# SCH_ESP32_Controller_PoE_2022-09-25.net
KiCad netlist of a schematic drawn in EasyEDA
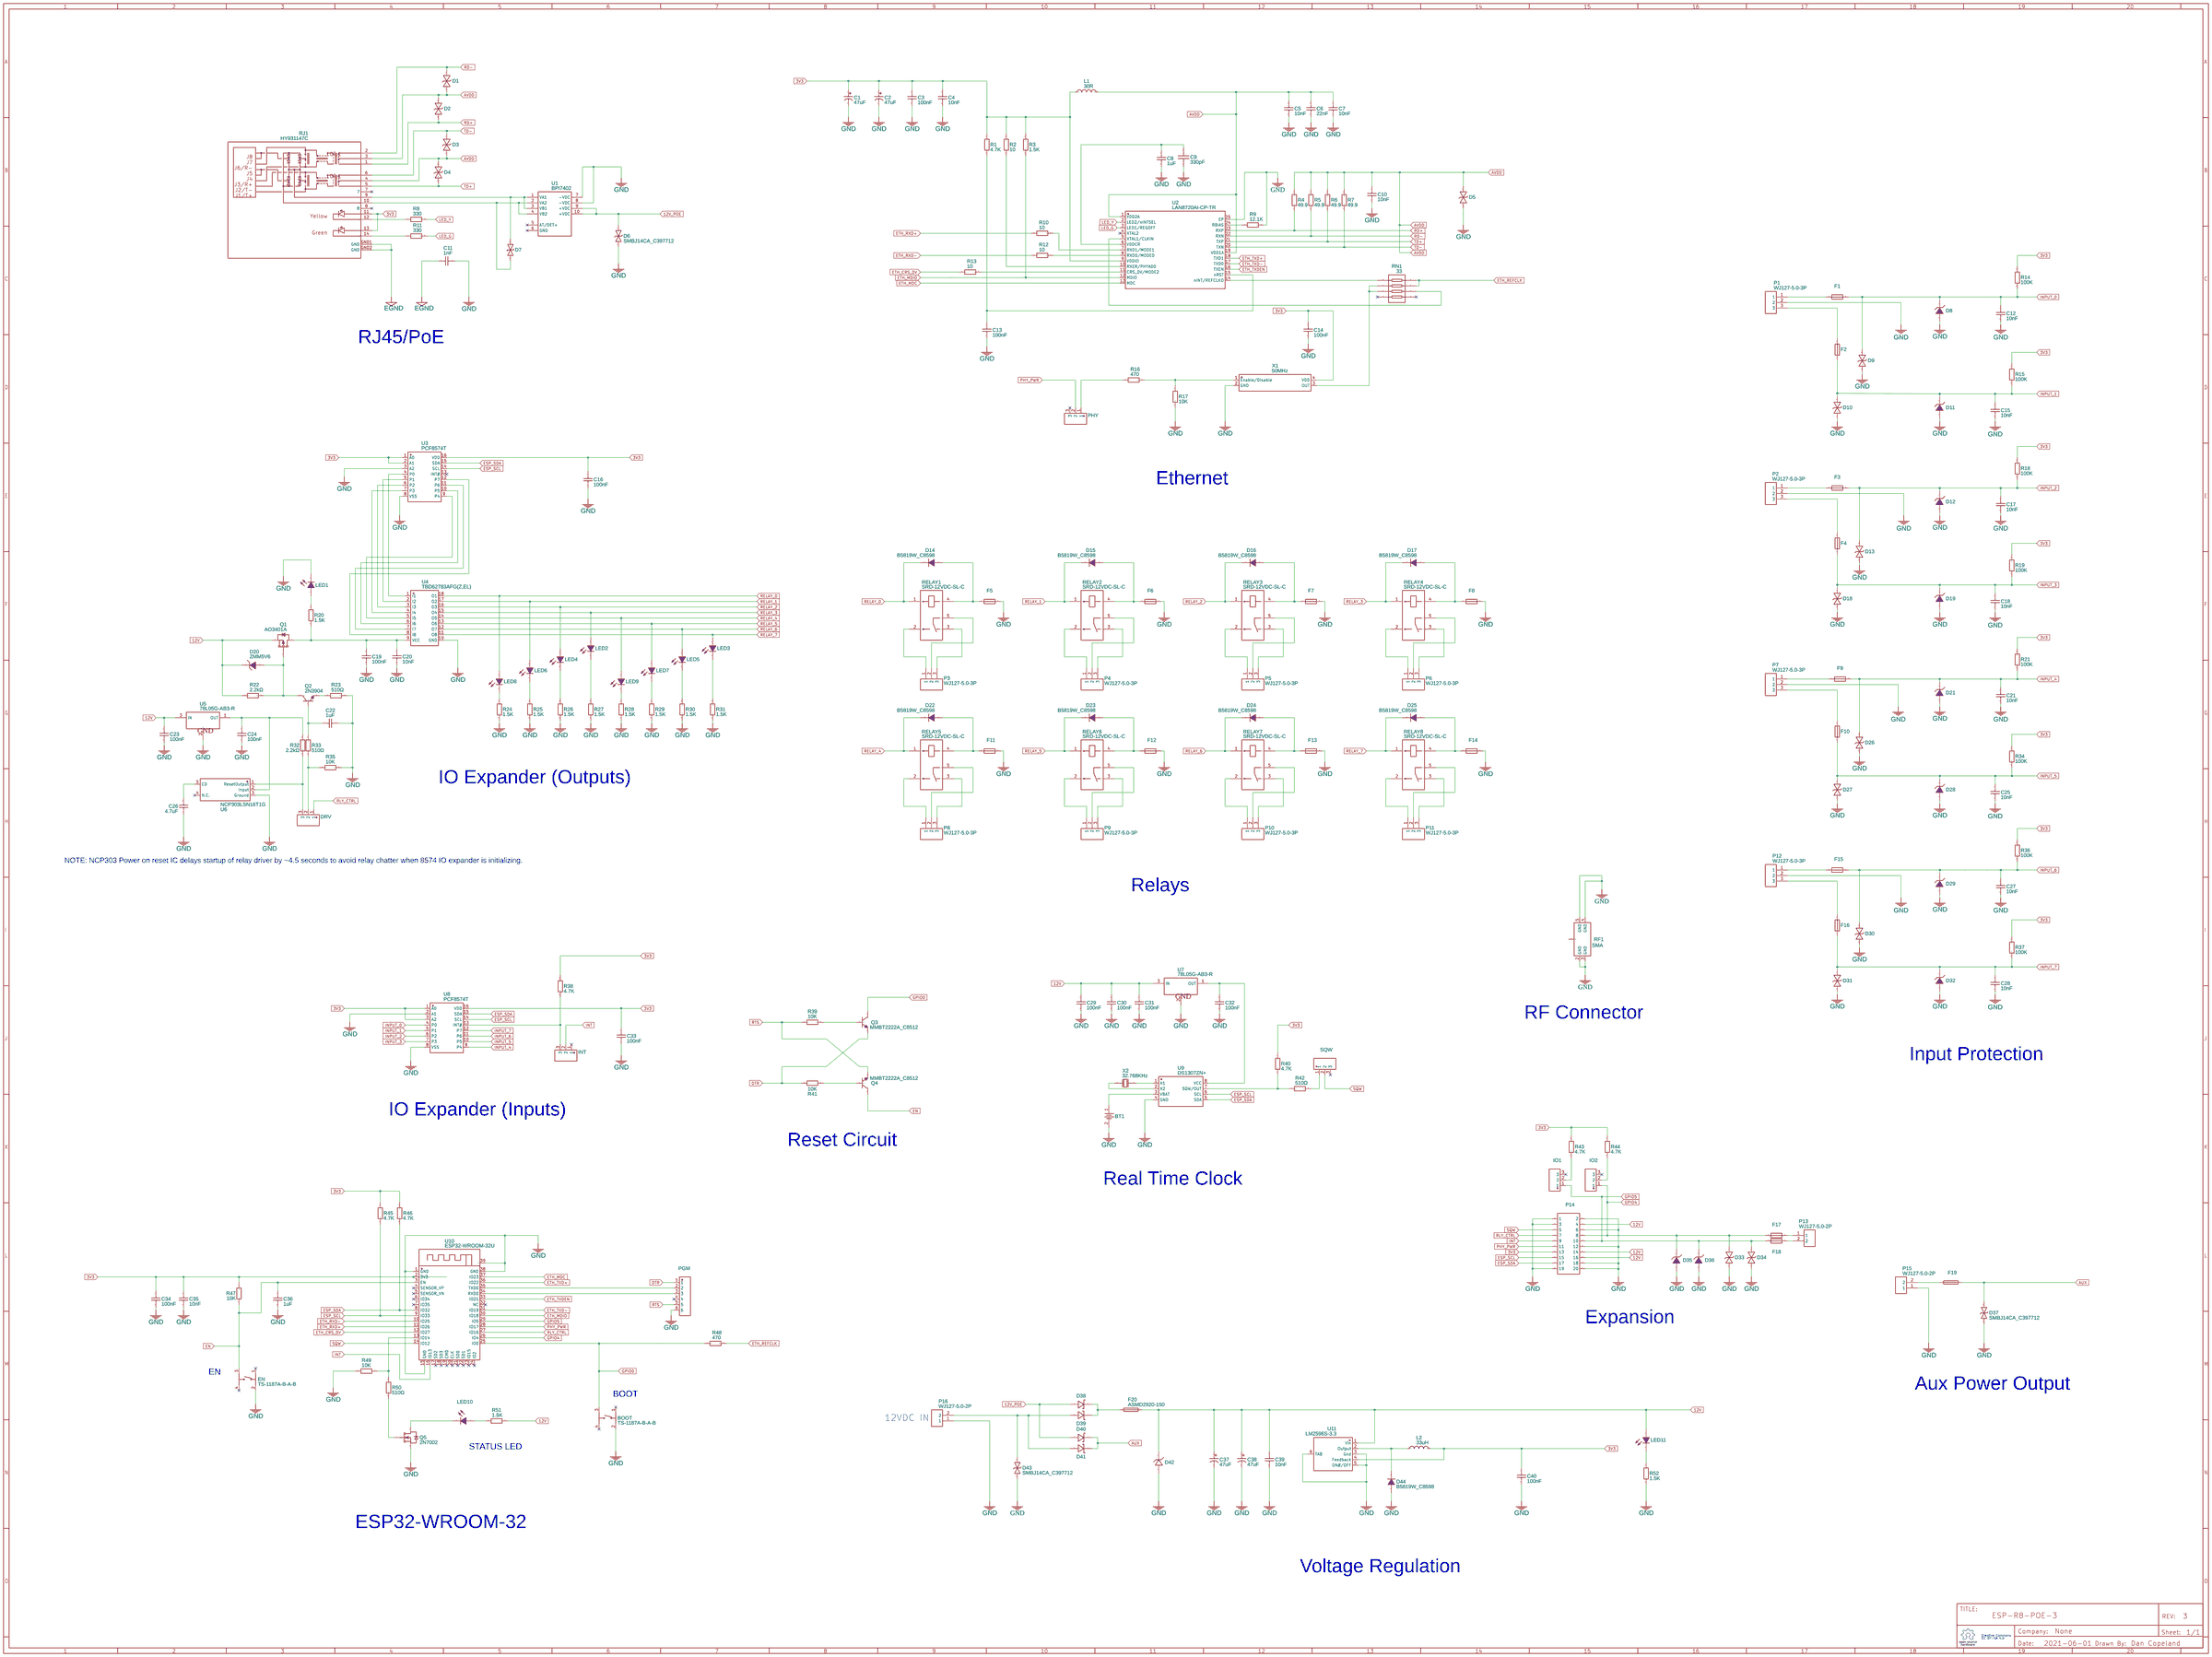
[diagram p0: schematic sheet]

(export (version "E")
  (design (tool "Eeschema 10.0.6"))
  (components
    (comp (ref "BOOT")
      (value "TS-1187A-B-A-B")
      (fields (field (name "BOM_Supplier Part") "C318884"))
      (libsource (lib "") (part "TS-1187A-B-A-B_1"))
    )
    (comp (ref "BT1")
      (value "BS-12-A1AJ002-F")
      (fields (field (name "BOM_Supplier Part") "C964720"))
      (libsource (lib "") (part "BS-12-A1AJ002-F"))
    )
    (comp (ref "C1")
      (value "47uF")
      (fields
        (field (name "BOM_Manufacturer Part") "16MS747MEFC5X7")
        (field (name "BOM_Supplier Part") "C108854")
      )
      (libsource (lib "") (part "16MS747MEFC5X7"))
    )
    (comp (ref "C2")
      (value "47uF")
      (fields
        (field (name "BOM_Manufacturer Part") "16MS747MEFC5X7")
        (field (name "BOM_Supplier Part") "C108854")
      )
      (libsource (lib "") (part "16MS747MEFC5X7"))
    )
    (comp (ref "C3")
      (value "100nF")
      (fields
        (field (name "BOM_Manufacturer Part") "CL05B104KO5NNNC")
        (field (name "BOM_Supplier Part") "C1525")
      )
      (libsource (lib "") (part "CL05B104KO5NNNC"))
    )
    (comp (ref "C4")
      (value "10nF")
      (fields
        (field (name "BOM_Manufacturer Part") "CL05B103KB5NNNC")
        (field (name "BOM_Supplier Part") "C15195")
      )
      (libsource (lib "") (part "CL05B103KB5NNNC"))
    )
    (comp (ref "C5")
      (value "10nF")
      (fields
        (field (name "BOM_Manufacturer Part") "CL05B103KB5NNNC")
        (field (name "BOM_Supplier Part") "C15195")
      )
      (libsource (lib "") (part "CL05B103KB5NNNC"))
    )
    (comp (ref "C6")
      (value "22nF")
      (fields
        (field (name "BOM_Manufacturer Part") "0402B223K500NT")
        (field (name "BOM_Supplier Part") "C1532")
      )
      (libsource (lib "") (part "0402B223K500NT"))
    )
    (comp (ref "C7")
      (value "10nF")
      (fields
        (field (name "BOM_Manufacturer Part") "CL05B103KB5NNNC")
        (field (name "BOM_Supplier Part") "C15195")
      )
      (libsource (lib "") (part "CL05B103KB5NNNC"))
    )
    (comp (ref "C8")
      (value "1uF")
      (fields
        (field (name "BOM_Manufacturer Part") "CL10A105KB8NNNC")
        (field (name "BOM_Supplier Part") "C15849")
      )
      (libsource (lib "") (part "CL10A105KB8NNNC"))
    )
    (comp (ref "C9")
      (value "330pF")
      (fields
        (field (name "BOM_Manufacturer Part") "CL05C331JB5NNNC")
        (field (name "BOM_Supplier Part") "C13533")
      )
      (libsource (lib "") (part "CL05C331JB5NNNC"))
    )
    (comp (ref "C10")
      (value "10nF")
      (fields
        (field (name "BOM_Manufacturer Part") "CL05B103KB5NNNC")
        (field (name "BOM_Supplier Part") "C15195")
      )
      (libsource (lib "") (part "CL05B103KB5NNNC"))
    )
    (comp (ref "C11")
      (value "1nF")
      (fields
        (field (name "BOM_Manufacturer Part") "1206B102K202NT")
        (field (name "BOM_Supplier Part") "C9196")
      )
      (libsource (lib "") (part "1206B102K202NT"))
    )
    (comp (ref "C12")
      (value "10nF")
      (fields
        (field (name "BOM_Manufacturer Part") "CL05B103KB5NNNC")
        (field (name "BOM_Supplier Part") "C15195")
      )
      (libsource (lib "") (part "CL05B103KB5NNNC"))
    )
    (comp (ref "C13")
      (value "100nF")
      (fields
        (field (name "BOM_Manufacturer Part") "CL05B104KO5NNNC")
        (field (name "BOM_Supplier Part") "C1525")
      )
      (libsource (lib "") (part "CL05B104KO5NNNC"))
    )
    (comp (ref "C14")
      (value "100nF")
      (fields
        (field (name "BOM_Manufacturer Part") "CL05B104KO5NNNC")
        (field (name "BOM_Supplier Part") "C1525")
      )
      (libsource (lib "") (part "CL05B104KO5NNNC"))
    )
    (comp (ref "C15")
      (value "10nF")
      (fields
        (field (name "BOM_Manufacturer Part") "CL05B103KB5NNNC")
        (field (name "BOM_Supplier Part") "C15195")
      )
      (libsource (lib "") (part "CL05B103KB5NNNC"))
    )
    (comp (ref "C16")
      (value "100nF")
      (fields
        (field (name "BOM_Manufacturer Part") "CL05B104KO5NNNC")
        (field (name "BOM_Supplier Part") "C1525")
      )
      (libsource (lib "") (part "CL05B104KO5NNNC"))
    )
    (comp (ref "C17")
      (value "10nF")
      (fields
        (field (name "BOM_Manufacturer Part") "CL05B103KB5NNNC")
        (field (name "BOM_Supplier Part") "C15195")
      )
      (libsource (lib "") (part "CL05B103KB5NNNC"))
    )
    (comp (ref "C18")
      (value "10nF")
      (fields
        (field (name "BOM_Manufacturer Part") "CL05B103KB5NNNC")
        (field (name "BOM_Supplier Part") "C15195")
      )
      (libsource (lib "") (part "CL05B103KB5NNNC"))
    )
    (comp (ref "C19")
      (value "100nF")
      (fields
        (field (name "BOM_Manufacturer Part") "CL05B104KO5NNNC")
        (field (name "BOM_Supplier Part") "C1525")
      )
      (libsource (lib "") (part "CL05B104KO5NNNC"))
    )
    (comp (ref "C20")
      (value "10nF")
      (fields
        (field (name "BOM_Manufacturer Part") "CL21B103KBANNNC")
        (field (name "BOM_Supplier Part") "C1710")
      )
      (libsource (lib "") (part "CL21B103KBANNNC"))
    )
    (comp (ref "C21")
      (value "10nF")
      (fields
        (field (name "BOM_Manufacturer Part") "CL05B103KB5NNNC")
        (field (name "BOM_Supplier Part") "C15195")
      )
      (libsource (lib "") (part "CL05B103KB5NNNC"))
    )
    (comp (ref "C22")
      (value "1uF")
      (fields
        (field (name "BOM_Manufacturer Part") "CL10A105KB8NNNC")
        (field (name "BOM_Supplier Part") "C15849")
      )
      (libsource (lib "") (part "CL10A105KB8NNNC_1"))
    )
    (comp (ref "C23")
      (value "100nF")
      (fields
        (field (name "BOM_Manufacturer Part") "CL05B104KO5NNNC")
        (field (name "BOM_Supplier Part") "C1525")
      )
      (libsource (lib "") (part "CL05B104KO5NNNC"))
    )
    (comp (ref "C24")
      (value "100nF")
      (fields
        (field (name "BOM_Manufacturer Part") "CL05B104KO5NNNC")
        (field (name "BOM_Supplier Part") "C1525")
      )
      (libsource (lib "") (part "CL05B104KO5NNNC"))
    )
    (comp (ref "C25")
      (value "10nF")
      (fields
        (field (name "BOM_Manufacturer Part") "CL05B103KB5NNNC")
        (field (name "BOM_Supplier Part") "C15195")
      )
      (libsource (lib "") (part "CL05B103KB5NNNC"))
    )
    (comp (ref "C26")
      (value "4.7uF")
      (fields
        (field (name "BOM_Manufacturer Part") "1206B475K500NT")
        (field (name "BOM_Supplier Part") "C29823")
      )
      (libsource (lib "") (part "1206B475K500NT"))
    )
    (comp (ref "C27")
      (value "10nF")
      (fields
        (field (name "BOM_Manufacturer Part") "CL05B103KB5NNNC")
        (field (name "BOM_Supplier Part") "C15195")
      )
      (libsource (lib "") (part "CL05B103KB5NNNC"))
    )
    (comp (ref "C28")
      (value "10nF")
      (fields
        (field (name "BOM_Manufacturer Part") "CL05B103KB5NNNC")
        (field (name "BOM_Supplier Part") "C15195")
      )
      (libsource (lib "") (part "CL05B103KB5NNNC"))
    )
    (comp (ref "C29")
      (value "100nF")
      (fields
        (field (name "BOM_Manufacturer Part") "CL05B104KO5NNNC")
        (field (name "BOM_Supplier Part") "C1525")
      )
      (libsource (lib "") (part "CL05B104KO5NNNC"))
    )
    (comp (ref "C30")
      (value "100nF")
      (fields
        (field (name "BOM_Manufacturer Part") "CL05B104KO5NNNC")
        (field (name "BOM_Supplier Part") "C1525")
      )
      (libsource (lib "") (part "CL05B104KO5NNNC"))
    )
    (comp (ref "C31")
      (value "100nF")
      (fields
        (field (name "BOM_Manufacturer Part") "CL05B104KO5NNNC")
        (field (name "BOM_Supplier Part") "C1525")
      )
      (libsource (lib "") (part "CL05B104KO5NNNC"))
    )
    (comp (ref "C32")
      (value "100nF")
      (fields
        (field (name "BOM_Manufacturer Part") "CL05B104KO5NNNC")
        (field (name "BOM_Supplier Part") "C1525")
      )
      (libsource (lib "") (part "CL05B104KO5NNNC"))
    )
    (comp (ref "C33")
      (value "100nF")
      (fields
        (field (name "BOM_Manufacturer Part") "CL05B104KO5NNNC")
        (field (name "BOM_Supplier Part") "C1525")
      )
      (libsource (lib "") (part "CL05B104KO5NNNC"))
    )
    (comp (ref "C34")
      (value "100nF")
      (fields
        (field (name "BOM_Manufacturer Part") "CL05B104KO5NNNC")
        (field (name "BOM_Supplier Part") "C1525")
      )
      (libsource (lib "") (part "CL05B104KO5NNNC"))
    )
    (comp (ref "C35")
      (value "10nF")
      (fields
        (field (name "BOM_Manufacturer Part") "CL05B103KB5NNNC")
        (field (name "BOM_Supplier Part") "C15195")
      )
      (libsource (lib "") (part "CL05B103KB5NNNC"))
    )
    (comp (ref "C36")
      (value "1uF")
      (fields
        (field (name "BOM_Manufacturer Part") "CL10A105KB8NNNC")
        (field (name "BOM_Supplier Part") "C15849")
      )
      (libsource (lib "") (part "CL10A105KB8NNNC"))
    )
    (comp (ref "C37")
      (value "47uF")
      (fields
        (field (name "BOM_Manufacturer Part") "16MS747MEFC5X7")
        (field (name "BOM_Supplier Part") "C108854")
      )
      (libsource (lib "") (part "16MS747MEFC5X7"))
    )
    (comp (ref "C38")
      (value "47uF")
      (fields
        (field (name "BOM_Manufacturer Part") "16MS747MEFC5X7")
        (field (name "BOM_Supplier Part") "C108854")
      )
      (libsource (lib "") (part "16MS747MEFC5X7"))
    )
    (comp (ref "C39")
      (value "10nF")
      (fields
        (field (name "BOM_Manufacturer Part") "CL21B103KBANNNC")
        (field (name "BOM_Supplier Part") "C1710")
      )
      (libsource (lib "") (part "CL21B103KBANNNC"))
    )
    (comp (ref "C40")
      (value "100nF")
      (fields
        (field (name "BOM_Manufacturer Part") "CL05B104KO5NNNC")
        (field (name "BOM_Supplier Part") "C1525")
      )
      (libsource (lib "") (part "CL05B104KO5NNNC"))
    )
    (comp (ref "D1")
      (value "PESD03V32D-LC")
      (fields (field (name "BOM_Supplier Part") "C2912528"))
      (libsource (lib "") (part "PESD03V32D-LC"))
    )
    (comp (ref "D2")
      (value "PESD03V32D-LC")
      (fields (field (name "BOM_Supplier Part") "C2912528"))
      (libsource (lib "") (part "PESD03V32D-LC"))
    )
    (comp (ref "D3")
      (value "PESD03V32D-LC")
      (fields (field (name "BOM_Supplier Part") "C2912528"))
      (libsource (lib "") (part "PESD03V32D-LC"))
    )
    (comp (ref "D4")
      (value "PESD03V32D-LC")
      (fields (field (name "BOM_Supplier Part") "C2912528"))
      (libsource (lib "") (part "PESD03V32D-LC"))
    )
    (comp (ref "D5")
      (value "PESD03V32D-LC")
      (fields (field (name "BOM_Supplier Part") "C2912528"))
      (libsource (lib "") (part "PESD03V32D-LC"))
    )
    (comp (ref "D6")
      (value "SMBJ14CA_C397712")
      (fields (field (name "BOM_Manufacturer Part") "SMBJ14CA") (field (name "BOM_Supplier Part") "C397712"))
      (libsource (lib "") (part "SMBJ14CA_C397712"))
    )
    (comp (ref "D7")
      (value "SMBJ64CA")
      (fields (field (name "BOM_Supplier Part") "C123975"))
      (libsource (lib "") (part "SMBJ64CA_C123975"))
    )
    (comp (ref "D8")
      (value "ZMM3V3")
      (fields (field (name "BOM_Supplier Part") "C8056"))
      (libsource (lib "") (part "ZMM3V3"))
    )
    (comp (ref "D9")
      (value "PESD03V32D-LC")
      (fields (field (name "BOM_Supplier Part") "C2912528"))
      (libsource (lib "") (part "PESD03V32D-LC"))
    )
    (comp (ref "D10")
      (value "PESD03V32D-LC")
      (fields (field (name "BOM_Supplier Part") "C2912528"))
      (libsource (lib "") (part "PESD03V32D-LC"))
    )
    (comp (ref "D11")
      (value "ZMM3V3")
      (fields (field (name "BOM_Supplier Part") "C8056"))
      (libsource (lib "") (part "ZMM3V3"))
    )
    (comp (ref "D12")
      (value "ZMM3V3")
      (fields (field (name "BOM_Supplier Part") "C8056"))
      (libsource (lib "") (part "ZMM3V3"))
    )
    (comp (ref "D13")
      (value "PESD03V32D-LC")
      (fields (field (name "BOM_Supplier Part") "C2912528"))
      (libsource (lib "") (part "PESD03V32D-LC"))
    )
    (comp (ref "D14")
      (value "B5819W_C8598")
      (fields (field (name "BOM_Manufacturer Part") "B5819W") (field (name "BOM_Supplier Part") "C8598"))
      (libsource (lib "") (part "B5819W_C8598_1"))
    )
    (comp (ref "D15")
      (value "B5819W_C8598")
      (fields (field (name "BOM_Manufacturer Part") "B5819W") (field (name "BOM_Supplier Part") "C8598"))
      (libsource (lib "") (part "B5819W_C8598_1"))
    )
    (comp (ref "D16")
      (value "B5819W_C8598")
      (fields (field (name "BOM_Manufacturer Part") "B5819W") (field (name "BOM_Supplier Part") "C8598"))
      (libsource (lib "") (part "B5819W_C8598_1"))
    )
    (comp (ref "D17")
      (value "B5819W_C8598")
      (fields (field (name "BOM_Manufacturer Part") "B5819W") (field (name "BOM_Supplier Part") "C8598"))
      (libsource (lib "") (part "B5819W_C8598_1"))
    )
    (comp (ref "D18")
      (value "PESD03V32D-LC")
      (fields (field (name "BOM_Supplier Part") "C2912528"))
      (libsource (lib "") (part "PESD03V32D-LC"))
    )
    (comp (ref "D19")
      (value "ZMM3V3")
      (fields (field (name "BOM_Supplier Part") "C8056"))
      (libsource (lib "") (part "ZMM3V3"))
    )
    (comp (ref "D20")
      (value "ZMM5V6")
      (fields (field (name "BOM_Supplier Part") "C8062"))
      (libsource (lib "") (part "ZMM5V6"))
    )
    (comp (ref "D21")
      (value "ZMM3V3")
      (fields (field (name "BOM_Supplier Part") "C8056"))
      (libsource (lib "") (part "ZMM3V3"))
    )
    (comp (ref "D22")
      (value "B5819W_C8598")
      (fields (field (name "BOM_Manufacturer Part") "B5819W") (field (name "BOM_Supplier Part") "C8598"))
      (libsource (lib "") (part "B5819W_C8598_1"))
    )
    (comp (ref "D23")
      (value "B5819W_C8598")
      (fields (field (name "BOM_Manufacturer Part") "B5819W") (field (name "BOM_Supplier Part") "C8598"))
      (libsource (lib "") (part "B5819W_C8598_1"))
    )
    (comp (ref "D24")
      (value "B5819W_C8598")
      (fields (field (name "BOM_Manufacturer Part") "B5819W") (field (name "BOM_Supplier Part") "C8598"))
      (libsource (lib "") (part "B5819W_C8598_1"))
    )
    (comp (ref "D25")
      (value "B5819W_C8598")
      (fields (field (name "BOM_Manufacturer Part") "B5819W") (field (name "BOM_Supplier Part") "C8598"))
      (libsource (lib "") (part "B5819W_C8598_1"))
    )
    (comp (ref "D26")
      (value "PESD03V32D-LC")
      (fields (field (name "BOM_Supplier Part") "C2912528"))
      (libsource (lib "") (part "PESD03V32D-LC"))
    )
    (comp (ref "D27")
      (value "PESD03V32D-LC")
      (fields (field (name "BOM_Supplier Part") "C2912528"))
      (libsource (lib "") (part "PESD03V32D-LC"))
    )
    (comp (ref "D28")
      (value "ZMM3V3")
      (fields (field (name "BOM_Supplier Part") "C8056"))
      (libsource (lib "") (part "ZMM3V3"))
    )
    (comp (ref "D29")
      (value "ZMM3V3")
      (fields (field (name "BOM_Supplier Part") "C8056"))
      (libsource (lib "") (part "ZMM3V3"))
    )
    (comp (ref "D30")
      (value "PESD03V32D-LC")
      (fields (field (name "BOM_Supplier Part") "C2912528"))
      (libsource (lib "") (part "PESD03V32D-LC"))
    )
    (comp (ref "D31")
      (value "PESD03V32D-LC")
      (fields (field (name "BOM_Supplier Part") "C2912528"))
      (libsource (lib "") (part "PESD03V32D-LC"))
    )
    (comp (ref "D32")
      (value "ZMM3V3")
      (fields (field (name "BOM_Supplier Part") "C8056"))
      (libsource (lib "") (part "ZMM3V3"))
    )
    (comp (ref "D33")
      (value "PESD03V32D-LC")
      (fields (field (name "BOM_Supplier Part") "C2912528"))
      (libsource (lib "") (part "PESD03V32D-LC"))
    )
    (comp (ref "D34")
      (value "PESD03V32D-LC")
      (fields (field (name "BOM_Supplier Part") "C2912528"))
      (libsource (lib "") (part "PESD03V32D-LC"))
    )
    (comp (ref "D35")
      (value "ZMM3V3")
      (fields (field (name "BOM_Supplier Part") "C8056"))
      (libsource (lib "") (part "ZMM3V3"))
    )
    (comp (ref "D36")
      (value "ZMM3V3")
      (fields (field (name "BOM_Supplier Part") "C8056"))
      (libsource (lib "") (part "ZMM3V3"))
    )
    (comp (ref "D37")
      (value "SMBJ14CA_C397712")
      (fields (field (name "BOM_Manufacturer Part") "SMBJ14CA") (field (name "BOM_Supplier Part") "C397712"))
      (libsource (lib "") (part "SMBJ14CA_C397712"))
    )
    (comp (ref "D38")
      (value "SS34_C8678")
      (fields (field (name "BOM_Manufacturer Part") "SS34") (field (name "BOM_Supplier Part") "C8678"))
      (libsource (lib "") (part "SS34_C8678_1"))
    )
    (comp (ref "D39")
      (value "SS34_C8678")
      (fields (field (name "BOM_Manufacturer Part") "SS34") (field (name "BOM_Supplier Part") "C8678"))
      (libsource (lib "") (part "SS34_C8678"))
    )
    (comp (ref "D40")
      (value "SS34_C8678")
      (fields (field (name "BOM_Manufacturer Part") "SS34") (field (name "BOM_Supplier Part") "C8678"))
      (libsource (lib "") (part "SS34_C8678_1"))
    )
    (comp (ref "D41")
      (value "SS34_C8678")
      (fields (field (name "BOM_Manufacturer Part") "SS34") (field (name "BOM_Supplier Part") "C8678"))
      (libsource (lib "") (part "SS34_C8678"))
    )
    (comp (ref "D42")
      (value "2EZ13D5_C388131")
      (fields (field (name "BOM_Manufacturer Part") "2EZ13D5") (field (name "BOM_Supplier Part") "C388131"))
      (libsource (lib "") (part "2EZ13D5_C388131"))
    )
    (comp (ref "D43")
      (value "SMBJ14CA_C397712")
      (fields (field (name "BOM_Manufacturer Part") "SMBJ14CA") (field (name "BOM_Supplier Part") "C397712"))
      (libsource (lib "") (part "SMBJ14CA_C397712"))
    )
    (comp (ref "D44")
      (value "B5819W_C8598")
      (fields (field (name "BOM_Manufacturer Part") "B5819W") (field (name "BOM_Supplier Part") "C8598"))
      (libsource (lib "") (part "B5819W_C8598"))
    )
    (comp (ref "DRV")
      (value "X1311WV-03J-C18D27")
      (fields (field (name "BOM_Supplier Part") "C2881648"))
      (libsource (lib "") (part "X1311WV-03J-C18D27_1"))
    )
    (comp (ref "EN")
      (value "TS-1187A-B-A-B")
      (fields (field (name "BOM_Supplier Part") "C318884"))
      (libsource (lib "") (part "TS-1187A-B-A-B"))
    )
    (comp (ref "F1")
      (value "BSMD0603-002-60V")
      (fields (field (name "BOM_Supplier Part") "C914089"))
      (libsource (lib "") (part "BSMD0603-002-60V_1"))
    )
    (comp (ref "F2")
      (value "BSMD0603-002-60V")
      (fields (field (name "BOM_Supplier Part") "C914089"))
      (libsource (lib "") (part "BSMD0603-002-60V"))
    )
    (comp (ref "F3")
      (value "BSMD0603-002-60V")
      (fields (field (name "BOM_Supplier Part") "C914089"))
      (libsource (lib "") (part "BSMD0603-002-60V_1"))
    )
    (comp (ref "F4")
      (value "BSMD0603-002-60V")
      (fields (field (name "BOM_Supplier Part") "C914089"))
      (libsource (lib "") (part "BSMD0603-002-60V"))
    )
    (comp (ref "F5")
      (value "BSMD0603-025-16V")
      (fields (field (name "BOM_Supplier Part") "C883094"))
      (libsource (lib "") (part "BSMD0603-025-16V"))
    )
    (comp (ref "F6")
      (value "BSMD0603-025-16V")
      (fields (field (name "BOM_Supplier Part") "C883094"))
      (libsource (lib "") (part "BSMD0603-025-16V"))
    )
    (comp (ref "F7")
      (value "BSMD0603-025-16V")
      (fields (field (name "BOM_Supplier Part") "C883094"))
      (libsource (lib "") (part "BSMD0603-025-16V"))
    )
    (comp (ref "F8")
      (value "BSMD0603-025-16V")
      (fields (field (name "BOM_Supplier Part") "C883094"))
      (libsource (lib "") (part "BSMD0603-025-16V"))
    )
    (comp (ref "F9")
      (value "BSMD0603-002-60V")
      (fields (field (name "BOM_Supplier Part") "C914089"))
      (libsource (lib "") (part "BSMD0603-002-60V_1"))
    )
    (comp (ref "F10")
      (value "BSMD0603-002-60V")
      (fields (field (name "BOM_Supplier Part") "C914089"))
      (libsource (lib "") (part "BSMD0603-002-60V"))
    )
    (comp (ref "F11")
      (value "BSMD0603-025-16V")
      (fields (field (name "BOM_Supplier Part") "C883094"))
      (libsource (lib "") (part "BSMD0603-025-16V"))
    )
    (comp (ref "F12")
      (value "BSMD0603-025-16V")
      (fields (field (name "BOM_Supplier Part") "C883094"))
      (libsource (lib "") (part "BSMD0603-025-16V"))
    )
    (comp (ref "F13")
      (value "BSMD0603-025-16V")
      (fields (field (name "BOM_Supplier Part") "C883094"))
      (libsource (lib "") (part "BSMD0603-025-16V"))
    )
    (comp (ref "F14")
      (value "BSMD0603-025-16V")
      (fields (field (name "BOM_Supplier Part") "C883094"))
      (libsource (lib "") (part "BSMD0603-025-16V"))
    )
    (comp (ref "F15")
      (value "BSMD0603-002-60V")
      (fields (field (name "BOM_Supplier Part") "C914089"))
      (libsource (lib "") (part "BSMD0603-002-60V_1"))
    )
    (comp (ref "F16")
      (value "BSMD0603-002-60V")
      (fields (field (name "BOM_Supplier Part") "C914089"))
      (libsource (lib "") (part "BSMD0603-002-60V"))
    )
    (comp (ref "F17")
      (value "BSMD0603-002-60V")
      (fields (field (name "BOM_Supplier Part") "C914089"))
      (libsource (lib "") (part "BSMD0603-002-60V_1"))
    )
    (comp (ref "F18")
      (value "BSMD0603-002-60V")
      (fields (field (name "BOM_Supplier Part") "C914089"))
      (libsource (lib "") (part "BSMD0603-002-60V_1"))
    )
    (comp (ref "F19")
      (value "ASMD2920-075")
      (fields (field (name "BOM_Supplier Part") "C135375"))
      (libsource (lib "") (part "ASMD2920-075"))
    )
    (comp (ref "F20")
      (value "ASMD2920-150")
      (fields (field (name "BOM_Supplier Part") "C135378"))
      (libsource (lib "") (part "ASMD2920-150"))
    )
    (comp (ref "INT")
      (value "X1311WV-03J-C18D27")
      (fields (field (name "BOM_Supplier Part") "C2881648"))
      (libsource (lib "") (part "X1311WV-03J-C18D27"))
    )
    (comp (ref "IO1")
      (value "X1311WV-03J-C18D27")
      (fields (field (name "BOM_Supplier Part") "C2881648"))
      (libsource (lib "") (part "X1311WV-03J-C18D27_3"))
    )
    (comp (ref "IO2")
      (value "X1311WV-03J-C18D27")
      (fields (field (name "BOM_Supplier Part") "C2881648"))
      (libsource (lib "") (part "X1311WV-03J-C18D27_3"))
    )
    (comp (ref "L1")
      (value "30R")
      (fields
        (field (name "BOM_Manufacturer Part") "SBM2012G300LSP")
        (field (name "BOM_Supplier Part") "C216133")
      )
      (libsource (lib "") (part "SBM2012G300LSP"))
    )
    (comp (ref "L2")
      (value "33uH")
      (fields
        (field (name "BOM_Manufacturer Part") "VLU0810-330K")
        (field (name "BOM_Supplier Part") "C72622")
      )
      (libsource (lib "") (part "VLU0810-330K"))
    )
    (comp (ref "LED1")
      (value "19-217/BHC-ZL1M2RY/3T")
      (fields (field (name "BOM_Supplier Part") "C72041"))
      (libsource (lib "") (part "19-217/BHC-ZL1M2RY/3T_1"))
    )
    (comp (ref "LED2")
      (value "19-217/BHC-ZL1M2RY/3T")
      (fields (field (name "BOM_Supplier Part") "C72041"))
      (libsource (lib "") (part "19-217/BHC-ZL1M2RY/3T"))
    )
    (comp (ref "LED3")
      (value "19-217/BHC-ZL1M2RY/3T")
      (fields (field (name "BOM_Supplier Part") "C72041"))
      (libsource (lib "") (part "19-217/BHC-ZL1M2RY/3T"))
    )
    (comp (ref "LED4")
      (value "19-217/BHC-ZL1M2RY/3T")
      (fields (field (name "BOM_Supplier Part") "C72041"))
      (libsource (lib "") (part "19-217/BHC-ZL1M2RY/3T"))
    )
    (comp (ref "LED5")
      (value "19-217/BHC-ZL1M2RY/3T")
      (fields (field (name "BOM_Supplier Part") "C72041"))
      (libsource (lib "") (part "19-217/BHC-ZL1M2RY/3T"))
    )
    (comp (ref "LED6")
      (value "19-217/BHC-ZL1M2RY/3T")
      (fields (field (name "BOM_Supplier Part") "C72041"))
      (libsource (lib "") (part "19-217/BHC-ZL1M2RY/3T"))
    )
    (comp (ref "LED7")
      (value "19-217/BHC-ZL1M2RY/3T")
      (fields (field (name "BOM_Supplier Part") "C72041"))
      (libsource (lib "") (part "19-217/BHC-ZL1M2RY/3T"))
    )
    (comp (ref "LED8")
      (value "19-217/BHC-ZL1M2RY/3T")
      (fields (field (name "BOM_Supplier Part") "C72041"))
      (libsource (lib "") (part "19-217/BHC-ZL1M2RY/3T"))
    )
    (comp (ref "LED9")
      (value "19-217/BHC-ZL1M2RY/3T")
      (fields (field (name "BOM_Supplier Part") "C72041"))
      (libsource (lib "") (part "19-217/BHC-ZL1M2RY/3T"))
    )
    (comp (ref "LED10")
      (value "19-217/BHC-ZL1M2RY/3T")
      (fields (field (name "BOM_Supplier Part") "C72041"))
      (libsource (lib "") (part "19-217/BHC-ZL1M2RY/3T_2"))
    )
    (comp (ref "LED11")
      (value "19-217/BHC-ZL1M2RY/3T")
      (fields (field (name "BOM_Supplier Part") "C72041"))
      (libsource (lib "") (part "19-217/BHC-ZL1M2RY/3T"))
    )
    (comp (ref "P1")
      (value "WJ127-5.0-3P")
      (fields (field (name "BOM_Supplier Part") "C8393"))
      (libsource (lib "") (part "WJ127-5.0-3P"))
    )
    (comp (ref "P2")
      (value "WJ127-5.0-3P")
      (fields (field (name "BOM_Supplier Part") "C8393"))
      (libsource (lib "") (part "WJ127-5.0-3P"))
    )
    (comp (ref "P3")
      (value "WJ127-5.0-3P")
      (fields (field (name "BOM_Supplier Part") "C8393"))
      (libsource (lib "") (part "WJ127-5.0-3P_1"))
    )
    (comp (ref "P4")
      (value "WJ127-5.0-3P")
      (fields (field (name "BOM_Supplier Part") "C8393"))
      (libsource (lib "") (part "WJ127-5.0-3P_1"))
    )
    (comp (ref "P5")
      (value "WJ127-5.0-3P")
      (fields (field (name "BOM_Supplier Part") "C8393"))
      (libsource (lib "") (part "WJ127-5.0-3P_1"))
    )
    (comp (ref "P6")
      (value "WJ127-5.0-3P")
      (fields (field (name "BOM_Supplier Part") "C8393"))
      (libsource (lib "") (part "WJ127-5.0-3P_1"))
    )
    (comp (ref "P7")
      (value "WJ127-5.0-3P")
      (fields (field (name "BOM_Supplier Part") "C8393"))
      (libsource (lib "") (part "WJ127-5.0-3P"))
    )
    (comp (ref "P8")
      (value "WJ127-5.0-3P")
      (fields (field (name "BOM_Supplier Part") "C8393"))
      (libsource (lib "") (part "WJ127-5.0-3P_1"))
    )
    (comp (ref "P9")
      (value "WJ127-5.0-3P")
      (fields (field (name "BOM_Supplier Part") "C8393"))
      (libsource (lib "") (part "WJ127-5.0-3P_1"))
    )
    (comp (ref "P10")
      (value "WJ127-5.0-3P")
      (fields (field (name "BOM_Supplier Part") "C8393"))
      (libsource (lib "") (part "WJ127-5.0-3P_1"))
    )
    (comp (ref "P11")
      (value "WJ127-5.0-3P")
      (fields (field (name "BOM_Supplier Part") "C8393"))
      (libsource (lib "") (part "WJ127-5.0-3P_1"))
    )
    (comp (ref "P12")
      (value "WJ127-5.0-3P")
      (fields (field (name "BOM_Supplier Part") "C8393"))
      (libsource (lib "") (part "WJ127-5.0-3P"))
    )
    (comp (ref "P13")
      (value "WJ127-5.0-2P")
      (fields (field (name "BOM_Supplier Part") "C3703"))
      (libsource (lib "") (part "WJ127-5.0-2P"))
    )
    (comp (ref "P14")
      (value "Header-Female-2.54_2x10")
      (fields
        (field (name "BOM_Manufacturer Part") "2.54mm,2×10Double row female")
        (field (name "BOM_Supplier Part") "C30867")
      )
      (libsource (lib "") (part "Header-Female-2.54_2x10"))
    )
    (comp (ref "P15")
      (value "WJ127-5.0-2P")
      (fields (field (name "BOM_Supplier Part") "C3703"))
      (libsource (lib "") (part "WJ127-5.0-2P_1"))
    )
    (comp (ref "P16")
      (value "WJ127-5.0-2P")
      (fields (field (name "BOM_Supplier Part") "C3703"))
      (libsource (lib "") (part "WJ127-5.0-2P_1"))
    )
    (comp (ref "PGM")
      (value "PZ254V-11-06P")
      (fields (field (name "BOM_Supplier Part") "C492405"))
      (libsource (lib "") (part "PZ254V-11-06P"))
    )
    (comp (ref "PHY")
      (value "X1311WV-03J-C18D27")
      (fields (field (name "BOM_Supplier Part") "C2881648"))
      (libsource (lib "") (part "X1311WV-03J-C18D27_2"))
    )
    (comp (ref "Q1")
      (value "AO3401A")
      (fields (field (name "BOM_Supplier Part") "C15127"))
      (libsource (lib "") (part "AO3401A"))
    )
    (comp (ref "Q2")
      (value "2N3904")
      (fields (field (name "BOM_Manufacturer Part") "MMBT3904") (field (name "BOM_Supplier Part") "C20526"))
      (libsource (lib "") (part "MMBT3904-C20526"))
    )
    (comp (ref "Q3")
      (value "MMBT2222A_C8512")
      (fields (field (name "BOM_Manufacturer Part") "MMBT2222A") (field (name "BOM_Supplier Part") "C8512"))
      (libsource (lib "") (part "MMBT2222A_C8512_1"))
    )
    (comp (ref "Q4")
      (value "MMBT2222A_C8512")
      (fields (field (name "BOM_Manufacturer Part") "MMBT2222A") (field (name "BOM_Supplier Part") "C8512"))
      (libsource (lib "") (part "MMBT2222A_C8512"))
    )
    (comp (ref "Q5")
      (value "2N7002")
      (fields (field (name "BOM_Supplier Part") "C8545"))
      (libsource (lib "") (part "2N7002"))
    )
    (comp (ref "R1")
      (value "4.7K")
      (fields
        (field (name "BOM_Manufacturer Part") "0402WGF4701TCE")
        (field (name "BOM_Supplier Part") "C25900")
      )
      (libsource (lib "") (part "0402WGF4701TCE"))
    )
    (comp (ref "R2")
      (value "10")
      (fields
        (field (name "BOM_Manufacturer Part") "0402WGF100JTCE")
        (field (name "BOM_Supplier Part") "C25077")
      )
      (libsource (lib "") (part "0402WGF100JTCE"))
    )
    (comp (ref "R3")
      (value "1.5K")
      (fields
        (field (name "BOM_Manufacturer Part") "0402WGF1501TCE")
        (field (name "BOM_Supplier Part") "C25867")
      )
      (libsource (lib "") (part "0402WGF1501TCE"))
    )
    (comp (ref "R4")
      (value "49.9")
      (fields
        (field (name "BOM_Manufacturer Part") "0402WGF499JTCE")
        (field (name "BOM_Supplier Part") "C25120")
      )
      (libsource (lib "") (part "0402WGF499JTCE"))
    )
    (comp (ref "R5")
      (value "49.9")
      (fields
        (field (name "BOM_Manufacturer Part") "0402WGF499JTCE")
        (field (name "BOM_Supplier Part") "C25120")
      )
      (libsource (lib "") (part "0402WGF499JTCE"))
    )
    (comp (ref "R6")
      (value "49.9")
      (fields
        (field (name "BOM_Manufacturer Part") "0402WGF499JTCE")
        (field (name "BOM_Supplier Part") "C25120")
      )
      (libsource (lib "") (part "0402WGF499JTCE"))
    )
    (comp (ref "R7")
      (value "49.9")
      (fields
        (field (name "BOM_Manufacturer Part") "0402WGF499JTCE")
        (field (name "BOM_Supplier Part") "C25120")
      )
      (libsource (lib "") (part "0402WGF499JTCE"))
    )
    (comp (ref "R8")
      (value "330")
      (fields
        (field (name "BOM_Manufacturer Part") "0402WGF3300TCE")
        (field (name "BOM_Supplier Part") "C25104")
      )
      (libsource (lib "") (part "0402WGF3300TCE"))
    )
    (comp (ref "R9")
      (value "12.1K")
      (fields
        (field (name "BOM_Manufacturer Part") "0402WGF1212TCE")
        (field (name "BOM_Supplier Part") "C25852")
      )
      (libsource (lib "") (part "0402WGF1212TCE"))
    )
    (comp (ref "R10")
      (value "10")
      (fields
        (field (name "BOM_Manufacturer Part") "0402WGF100JTCE")
        (field (name "BOM_Supplier Part") "C25077")
      )
      (libsource (lib "") (part "0402WGF100JTCE_1"))
    )
    (comp (ref "R11")
      (value "330")
      (fields
        (field (name "BOM_Manufacturer Part") "0402WGF3300TCE")
        (field (name "BOM_Supplier Part") "C25104")
      )
      (libsource (lib "") (part "0402WGF3300TCE"))
    )
    (comp (ref "R12")
      (value "10")
      (fields
        (field (name "BOM_Manufacturer Part") "0402WGF100JTCE")
        (field (name "BOM_Supplier Part") "C25077")
      )
      (libsource (lib "") (part "0402WGF100JTCE_1"))
    )
    (comp (ref "R13")
      (value "10")
      (fields
        (field (name "BOM_Manufacturer Part") "0402WGF100JTCE")
        (field (name "BOM_Supplier Part") "C25077")
      )
      (libsource (lib "") (part "0402WGF100JTCE_1"))
    )
    (comp (ref "R14")
      (value "100K")
      (fields
        (field (name "BOM_Manufacturer Part") "0402WGF1003TCE")
        (field (name "BOM_Supplier Part") "C25741")
      )
      (libsource (lib "") (part "0402WGF1003TCE"))
    )
    (comp (ref "R15")
      (value "100K")
      (fields
        (field (name "BOM_Manufacturer Part") "0402WGF1003TCE")
        (field (name "BOM_Supplier Part") "C25741")
      )
      (libsource (lib "") (part "0402WGF1003TCE"))
    )
    (comp (ref "R16")
      (value "470")
      (fields
        (field (name "BOM_Manufacturer Part") "0402WGF4700TCE")
        (field (name "BOM_Supplier Part") "C25117")
      )
      (libsource (lib "") (part "0402WGF4700TCE"))
    )
    (comp (ref "R17")
      (value "10K")
      (fields
        (field (name "BOM_Manufacturer Part") "0402WGF1002TCE")
        (field (name "BOM_Supplier Part") "C25744")
      )
      (libsource (lib "") (part "0402WGF1002TCE_1"))
    )
    (comp (ref "R18")
      (value "100K")
      (fields
        (field (name "BOM_Manufacturer Part") "0402WGF1003TCE")
        (field (name "BOM_Supplier Part") "C25741")
      )
      (libsource (lib "") (part "0402WGF1003TCE"))
    )
    (comp (ref "R19")
      (value "100K")
      (fields
        (field (name "BOM_Manufacturer Part") "0402WGF1003TCE")
        (field (name "BOM_Supplier Part") "C25741")
      )
      (libsource (lib "") (part "0402WGF1003TCE"))
    )
    (comp (ref "R20")
      (value "1.5K")
      (fields
        (field (name "BOM_Manufacturer Part") "0603WAF1501T5E")
        (field (name "BOM_Supplier Part") "C22843")
      )
      (libsource (lib "") (part "0603WAF1501T5E"))
    )
    (comp (ref "R21")
      (value "100K")
      (fields
        (field (name "BOM_Manufacturer Part") "0402WGF1003TCE")
        (field (name "BOM_Supplier Part") "C25741")
      )
      (libsource (lib "") (part "0402WGF1003TCE"))
    )
    (comp (ref "R22")
      (value "2.2kΩ")
      (fields
        (field (name "BOM_Manufacturer Part") "0402WGF2201TCE")
        (field (name "BOM_Supplier Part") "C25879")
      )
      (libsource (lib "") (part "0402WGF2201TCE_1"))
    )
    (comp (ref "R23")
      (value "510Ω")
      (fields
        (field (name "BOM_Manufacturer Part") "0402WGF5100TCE")
        (field (name "BOM_Supplier Part") "C25123")
      )
      (libsource (lib "") (part "0402WGF5100TCE_1"))
    )
    (comp (ref "R24")
      (value "1.5K")
      (fields
        (field (name "BOM_Manufacturer Part") "0603WAF1501T5E")
        (field (name "BOM_Supplier Part") "C22843")
      )
      (libsource (lib "") (part "0603WAF1501T5E"))
    )
    (comp (ref "R25")
      (value "1.5K")
      (fields
        (field (name "BOM_Manufacturer Part") "0603WAF1501T5E")
        (field (name "BOM_Supplier Part") "C22843")
      )
      (libsource (lib "") (part "0603WAF1501T5E"))
    )
    (comp (ref "R26")
      (value "1.5K")
      (fields
        (field (name "BOM_Manufacturer Part") "0603WAF1501T5E")
        (field (name "BOM_Supplier Part") "C22843")
      )
      (libsource (lib "") (part "0603WAF1501T5E"))
    )
    (comp (ref "R27")
      (value "1.5K")
      (fields
        (field (name "BOM_Manufacturer Part") "0603WAF1501T5E")
        (field (name "BOM_Supplier Part") "C22843")
      )
      (libsource (lib "") (part "0603WAF1501T5E"))
    )
    (comp (ref "R28")
      (value "1.5K")
      (fields
        (field (name "BOM_Manufacturer Part") "0603WAF1501T5E")
        (field (name "BOM_Supplier Part") "C22843")
      )
      (libsource (lib "") (part "0603WAF1501T5E"))
    )
    (comp (ref "R29")
      (value "1.5K")
      (fields
        (field (name "BOM_Manufacturer Part") "0603WAF1501T5E")
        (field (name "BOM_Supplier Part") "C22843")
      )
      (libsource (lib "") (part "0603WAF1501T5E"))
    )
    (comp (ref "R30")
      (value "1.5K")
      (fields
        (field (name "BOM_Manufacturer Part") "0603WAF1501T5E")
        (field (name "BOM_Supplier Part") "C22843")
      )
      (libsource (lib "") (part "0603WAF1501T5E"))
    )
    (comp (ref "R31")
      (value "1.5K")
      (fields
        (field (name "BOM_Manufacturer Part") "0603WAF1501T5E")
        (field (name "BOM_Supplier Part") "C22843")
      )
      (libsource (lib "") (part "0603WAF1501T5E"))
    )
    (comp (ref "R32")
      (value "2.2kΩ")
      (fields
        (field (name "BOM_Manufacturer Part") "0402WGF2201TCE")
        (field (name "BOM_Supplier Part") "C25879")
      )
      (libsource (lib "") (part "0402WGF2201TCE"))
    )
    (comp (ref "R33")
      (value "510Ω")
      (fields
        (field (name "BOM_Manufacturer Part") "0402WGF5100TCE")
        (field (name "BOM_Supplier Part") "C25123")
      )
      (libsource (lib "") (part "0402WGF5100TCE"))
    )
    (comp (ref "R34")
      (value "100K")
      (fields
        (field (name "BOM_Manufacturer Part") "0402WGF1003TCE")
        (field (name "BOM_Supplier Part") "C25741")
      )
      (libsource (lib "") (part "0402WGF1003TCE"))
    )
    (comp (ref "R35")
      (value "10K")
      (fields
        (field (name "BOM_Manufacturer Part") "0402WGF1002TCE")
        (field (name "BOM_Supplier Part") "C25744")
      )
      (libsource (lib "") (part "0402WGF1002TCE"))
    )
    (comp (ref "R36")
      (value "100K")
      (fields
        (field (name "BOM_Manufacturer Part") "0402WGF1003TCE")
        (field (name "BOM_Supplier Part") "C25741")
      )
      (libsource (lib "") (part "0402WGF1003TCE"))
    )
    (comp (ref "R37")
      (value "100K")
      (fields
        (field (name "BOM_Manufacturer Part") "0402WGF1003TCE")
        (field (name "BOM_Supplier Part") "C25741")
      )
      (libsource (lib "") (part "0402WGF1003TCE"))
    )
    (comp (ref "R38")
      (value "4.7K")
      (fields
        (field (name "BOM_Manufacturer Part") "0402WGF4701TCE")
        (field (name "BOM_Supplier Part") "C25900")
      )
      (libsource (lib "") (part "0402WGF4701TCE"))
    )
    (comp (ref "R39")
      (value "10K")
      (fields
        (field (name "BOM_Manufacturer Part") "0402WGF1002TCE")
        (field (name "BOM_Supplier Part") "C25744")
      )
      (libsource (lib "") (part "0402WGF1002TCE"))
    )
    (comp (ref "R40")
      (value "4.7K")
      (fields
        (field (name "BOM_Manufacturer Part") "0402WGF4701TCE")
        (field (name "BOM_Supplier Part") "C25900")
      )
      (libsource (lib "") (part "0402WGF4701TCE"))
    )
    (comp (ref "R41")
      (value "10K")
      (fields
        (field (name "BOM_Manufacturer Part") "0402WGF1002TCE")
        (field (name "BOM_Supplier Part") "C25744")
      )
      (libsource (lib "") (part "0402WGF1002TCE"))
    )
    (comp (ref "R42")
      (value "510Ω")
      (fields
        (field (name "BOM_Manufacturer Part") "0402WGF5100TCE")
        (field (name "BOM_Supplier Part") "C25123")
      )
      (libsource (lib "") (part "0402WGF5100TCE_1"))
    )
    (comp (ref "R43")
      (value "4.7K")
      (fields
        (field (name "BOM_Manufacturer Part") "0402WGF4701TCE")
        (field (name "BOM_Supplier Part") "C25900")
      )
      (libsource (lib "") (part "0402WGF4701TCE"))
    )
    (comp (ref "R44")
      (value "4.7K")
      (fields
        (field (name "BOM_Manufacturer Part") "0402WGF4701TCE")
        (field (name "BOM_Supplier Part") "C25900")
      )
      (libsource (lib "") (part "0402WGF4701TCE"))
    )
    (comp (ref "R45")
      (value "4.7K")
      (fields
        (field (name "BOM_Manufacturer Part") "0402WGF4701TCE")
        (field (name "BOM_Supplier Part") "C25900")
      )
      (libsource (lib "") (part "0402WGF4701TCE"))
    )
    (comp (ref "R46")
      (value "4.7K")
      (fields
        (field (name "BOM_Manufacturer Part") "0402WGF4701TCE")
        (field (name "BOM_Supplier Part") "C25900")
      )
      (libsource (lib "") (part "0402WGF4701TCE"))
    )
    (comp (ref "R47")
      (value "10K")
      (fields
        (field (name "BOM_Manufacturer Part") "0402WGF1002TCE")
        (field (name "BOM_Supplier Part") "C25744")
      )
      (libsource (lib "") (part "0402WGF1002TCE_1"))
    )
    (comp (ref "R48")
      (value "470")
      (fields
        (field (name "BOM_Manufacturer Part") "0402WGF4700TCE")
        (field (name "BOM_Supplier Part") "C25117")
      )
      (libsource (lib "") (part "0402WGF4700TCE"))
    )
    (comp (ref "R49")
      (value "10K")
      (fields
        (field (name "BOM_Manufacturer Part") "0402WGF1002TCE")
        (field (name "BOM_Supplier Part") "C25744")
      )
      (libsource (lib "") (part "0402WGF1002TCE"))
    )
    (comp (ref "R50")
      (value "510Ω")
      (fields
        (field (name "BOM_Manufacturer Part") "0402WGF5100TCE")
        (field (name "BOM_Supplier Part") "C25123")
      )
      (libsource (lib "") (part "0402WGF5100TCE"))
    )
    (comp (ref "R51")
      (value "1.5K")
      (fields
        (field (name "BOM_Manufacturer Part") "0603WAF1501T5E")
        (field (name "BOM_Supplier Part") "C22843")
      )
      (libsource (lib "") (part "0603WAF1501T5E_1"))
    )
    (comp (ref "R52")
      (value "1.5K")
      (fields
        (field (name "BOM_Manufacturer Part") "0603WAF1501T5E")
        (field (name "BOM_Supplier Part") "C22843")
      )
      (libsource (lib "") (part "0603WAF1501T5E"))
    )
    (comp (ref "RELAY1")
      (value "SRD-12VDC-SL-C")
      (fields (field (name "BOM_Supplier Part") "C30431"))
      (libsource (lib "") (part "SRD-12VDC-SL-C"))
    )
    (comp (ref "RELAY2")
      (value "SRD-12VDC-SL-C")
      (fields (field (name "BOM_Supplier Part") "C30431"))
      (libsource (lib "") (part "SRD-12VDC-SL-C"))
    )
    (comp (ref "RELAY3")
      (value "SRD-12VDC-SL-C")
      (fields (field (name "BOM_Supplier Part") "C30431"))
      (libsource (lib "") (part "SRD-12VDC-SL-C"))
    )
    (comp (ref "RELAY4")
      (value "SRD-12VDC-SL-C")
      (fields (field (name "BOM_Supplier Part") "C30431"))
      (libsource (lib "") (part "SRD-12VDC-SL-C"))
    )
    (comp (ref "RELAY5")
      (value "SRD-12VDC-SL-C")
      (fields (field (name "BOM_Supplier Part") "C30431"))
      (libsource (lib "") (part "SRD-12VDC-SL-C"))
    )
    (comp (ref "RELAY6")
      (value "SRD-12VDC-SL-C")
      (fields (field (name "BOM_Supplier Part") "C30431"))
      (libsource (lib "") (part "SRD-12VDC-SL-C"))
    )
    (comp (ref "RELAY7")
      (value "SRD-12VDC-SL-C")
      (fields (field (name "BOM_Supplier Part") "C30431"))
      (libsource (lib "") (part "SRD-12VDC-SL-C"))
    )
    (comp (ref "RELAY8")
      (value "SRD-12VDC-SL-C")
      (fields (field (name "BOM_Supplier Part") "C30431"))
      (libsource (lib "") (part "SRD-12VDC-SL-C"))
    )
    (comp (ref "RF1")
      (value "SMA")
      (fields
        (field (name "BOM_Manufacturer Part") "HJ-SMA200")
        (field (name "BOM_Supplier Part") "C1509215")
      )
      (libsource (lib "") (part "HJ-SMA200"))
    )
    (comp (ref "RJ1")
      (value "HY931147C")
      (fields (field (name "BOM_Supplier Part") "C91754"))
      (libsource (lib "") (part "HY931147C"))
    )
    (comp (ref "RN1")
      (value "33")
      (fields
        (field (name "BOM_Manufacturer Part") "4D02WGJ0330TCE")
        (field (name "BOM_Supplier Part") "C25501")
      )
      (libsource (lib "") (part "4D02WGJ0330TCE"))
    )
    (comp (ref "SQW")
      (value "X1311WV-03J-C18D27")
      (fields (field (name "BOM_Supplier Part") "C2881648"))
      (libsource (lib "") (part "X1311WV-03J-C18D27_4"))
    )
    (comp (ref "U1") (value "BPI7402") (libsource (lib "") (part "BPI7402")))
    (comp (ref "U2")
      (value "LAN8720AI-CP-TR")
      (fields (field (name "BOM_Supplier Part") "C17146"))
      (libsource (lib "") (part "LAN8720AI-CP-TR"))
    )
    (comp (ref "U3")
      (value "PCF8574T")
      (fields (field (name "BOM_Supplier Part") "C2973152"))
      (libsource (lib "") (part "PCF8574T_C2973152"))
    )
    (comp (ref "U4")
      (value "TBD62783AFG(Z,EL)")
      (fields (field (name "BOM_Supplier Part") "C840444"))
      (libsource (lib "") (part "TBD62783AFG(Z,EL)"))
    )
    (comp (ref "U5")
      (value "78L05G-AB3-R")
      (fields (field (name "BOM_Supplier Part") "C71136"))
      (libsource (lib "") (part "78L05G-AB3-R"))
    )
    (comp (ref "U6")
      (value "NCP303LSN16T1G")
      (fields (field (name "BOM_Supplier Part") "C892351"))
      (libsource (lib "") (part "NCP303LSN16T1G"))
    )
    (comp (ref "U7")
      (value "78L05G-AB3-R")
      (fields (field (name "BOM_Supplier Part") "C71136"))
      (libsource (lib "") (part "78L05G-AB3-R"))
    )
    (comp (ref "U8")
      (value "PCF8574T")
      (fields (field (name "BOM_Supplier Part") "C2973152"))
      (libsource (lib "") (part "PCF8574T_C2973152"))
    )
    (comp (ref "U9")
      (value "DS1307ZN+")
      (fields (field (name "BOM_Supplier Part") "C26858"))
      (libsource (lib "") (part "DS1307ZN+"))
    )
    (comp (ref "U10")
      (value "ESP32-WROOM-32U")
      (fields (field (name "BOM_Supplier Part") "C328062"))
      (libsource (lib "") (part "ESP32-WROOM-32U"))
    )
    (comp (ref "U11")
      (value "LM2596S-3.3")
      (fields (field (name "BOM_Supplier Part") "C347420"))
      (libsource (lib "") (part "LM2596S-3.3"))
    )
    (comp (ref "X1")
      (value "50MHz")
      (fields
        (field (name "BOM_Manufacturer Part") "OT705050MJBA4SL")
        (field (name "BOM_Supplier Part") "C669094")
      )
      (libsource (lib "") (part "OT705050MJBA4SL"))
    )
    (comp (ref "X2")
      (value "32.768KHz")
      (fields (field (name "BOM_Supplier Part") "C145164"))
      (libsource (lib "") (part "TDXLF-308 32.768KHZ 12.5PF 20PPM"))
    )
  )
  (nets
    (net (code "1") (name "3V3") (class "Default")
      (node (ref "C1") (pin "1") (pinfunction "1_1") (pintype "input"))
      (node (ref "C14") (pin "1") (pinfunction "1_1") (pintype "input"))
      (node (ref "C16") (pin "1") (pinfunction "1_1") (pintype "input"))
      (node (ref "C2") (pin "1") (pinfunction "1_1") (pintype "input"))
      (node (ref "C3") (pin "1") (pinfunction "1_1") (pintype "input"))
      (node (ref "C33") (pin "1") (pinfunction "1_1") (pintype "input"))
      (node (ref "C34") (pin "1") (pinfunction "1_1") (pintype "input"))
      (node (ref "C35") (pin "1") (pinfunction "1_1") (pintype "input"))
      (node (ref "C4") (pin "1") (pinfunction "1_1") (pintype "input"))
      (node (ref "C40") (pin "1") (pinfunction "1_1") (pintype "input"))
      (node (ref "L1") (pin "1") (pinfunction "1_1") (pintype "unspecified"))
      (node (ref "L2") (pin "2") (pinfunction "2_2") (pintype "unspecified"))
      (node (ref "P14") (pin "13") (pinfunction "13_13") (pintype "input"))
      (node (ref "R1") (pin "1") (pinfunction "1_1") (pintype "input"))
      (node (ref "R14") (pin "1") (pinfunction "1_1") (pintype "input"))
      (node (ref "R15") (pin "1") (pinfunction "1_1") (pintype "input"))
      (node (ref "R18") (pin "1") (pinfunction "1_1") (pintype "input"))
      (node (ref "R19") (pin "1") (pinfunction "1_1") (pintype "input"))
      (node (ref "R2") (pin "1") (pinfunction "1_1") (pintype "input"))
      (node (ref "R21") (pin "1") (pinfunction "1_1") (pintype "input"))
      (node (ref "R3") (pin "1") (pinfunction "1_1") (pintype "input"))
      (node (ref "R34") (pin "1") (pinfunction "1_1") (pintype "input"))
      (node (ref "R36") (pin "1") (pinfunction "1_1") (pintype "input"))
      (node (ref "R37") (pin "1") (pinfunction "1_1") (pintype "input"))
      (node (ref "R38") (pin "1") (pinfunction "1_1") (pintype "input"))
      (node (ref "R40") (pin "1") (pinfunction "1_1") (pintype "input"))
      (node (ref "R43") (pin "1") (pinfunction "1_1") (pintype "input"))
      (node (ref "R44") (pin "1") (pinfunction "1_1") (pintype "input"))
      (node (ref "R45") (pin "1") (pinfunction "1_1") (pintype "input"))
      (node (ref "R46") (pin "1") (pinfunction "1_1") (pintype "input"))
      (node (ref "R47") (pin "1") (pinfunction "1_1") (pintype "input"))
      (node (ref "RJ1") (pin "11") (pinfunction "11_11") (pintype "unspecified"))
      (node (ref "RJ1") (pin "13") (pinfunction "13_13") (pintype "unspecified"))
      (node (ref "U10") (pin "2") (pinfunction "3V3_2") (pintype "unspecified"))
      (node (ref "U11") (pin "4") (pinfunction "Feedback_4") (pintype "unspecified"))
      (node (ref "U2") (pin "9") (pinfunction "VDDIO_9") (pintype "unspecified"))
      (node (ref "U3") (pin "1") (pinfunction "A0_1") (pintype "unspecified"))
      (node (ref "U3") (pin "16") (pinfunction "VDD_16") (pintype "unspecified"))
      (node (ref "U3") (pin "2") (pinfunction "A1_2") (pintype "unspecified"))
      (node (ref "U8") (pin "1") (pinfunction "A0_1") (pintype "unspecified"))
      (node (ref "U8") (pin "16") (pinfunction "VDD_16") (pintype "unspecified"))
      (node (ref "U8") (pin "3") (pinfunction "A2_3") (pintype "unspecified"))
      (node (ref "X1") (pin "4") (pinfunction "VDD_4") (pintype "unspecified"))
    )
    (net (code "2") (name "12V") (class "Default")
      (node (ref "C23") (pin "1") (pinfunction "1_1") (pintype "input"))
      (node (ref "C29") (pin "1") (pinfunction "1_1") (pintype "input"))
      (node (ref "C30") (pin "1") (pinfunction "1_1") (pintype "input"))
      (node (ref "C31") (pin "1") (pinfunction "1_1") (pintype "input"))
      (node (ref "C37") (pin "1") (pinfunction "1_1") (pintype "input"))
      (node (ref "C38") (pin "1") (pinfunction "1_1") (pintype "input"))
      (node (ref "C39") (pin "1") (pinfunction "1_1") (pintype "input"))
      (node (ref "D20") (pin "1") (pinfunction "C_1") (pintype "unspecified"))
      (node (ref "D42") (pin "1") (pinfunction "C_1") (pintype "unspecified"))
      (node (ref "F20") (pin "2") (pinfunction "2_2") (pintype "unspecified"))
      (node (ref "LED11") (pin "1") (pinfunction "A_1") (pintype "input"))
      (node (ref "P14") (pin "14") (pinfunction "14_14") (pintype "input"))
      (node (ref "P14") (pin "16") (pinfunction "16_16") (pintype "input"))
      (node (ref "P14") (pin "4") (pinfunction "4_4") (pintype "input"))
      (node (ref "Q1") (pin "2") (pinfunction "S_2") (pintype "unspecified"))
      (node (ref "R22") (pin "1") (pinfunction "1_1") (pintype "input"))
      (node (ref "R51") (pin "1") (pinfunction "1_1") (pintype "input"))
      (node (ref "U11") (pin "1") (pinfunction "Vin_1") (pintype "unspecified"))
      (node (ref "U5") (pin "3") (pinfunction "IN_3") (pintype "passive"))
      (node (ref "U7") (pin "3") (pinfunction "IN_3") (pintype "passive"))
    )
    (net (code "3") (name "12V_POE") (class "Default")
      (node (ref "D38") (pin "2") (pinfunction "A_2") (pintype "unspecified"))
      (node (ref "D40") (pin "2") (pinfunction "A_2") (pintype "unspecified"))
      (node (ref "D6") (pin "1") (pinfunction "1_1") (pintype "unspecified"))
      (node (ref "U1") (pin "10") (pinfunction "+VDC_10") (pintype "unspecified"))
      (node (ref "U1") (pin "9") (pinfunction "+VDC_9") (pintype "unspecified"))
    )
    (net (code "4") (name "AUX") (class "Default")
      (node (ref "D37") (pin "1") (pinfunction "1_1") (pintype "unspecified"))
      (node (ref "D40") (pin "1") (pinfunction "K_1") (pintype "unspecified"))
      (node (ref "D41") (pin "1") (pinfunction "K_1") (pintype "unspecified"))
      (node (ref "F19") (pin "2") (pinfunction "2_2") (pintype "unspecified"))
    )
    (net (code "5") (name "AVDD") (class "Default")
      (node (ref "C10") (pin "1") (pinfunction "1_1") (pintype "input"))
      (node (ref "C5") (pin "1") (pinfunction "1_1") (pintype "input"))
      (node (ref "C6") (pin "1") (pinfunction "1_1") (pintype "input"))
      (node (ref "C7") (pin "1") (pinfunction "1_1") (pintype "input"))
      (node (ref "D1") (pin "2") (pinfunction "2_2") (pintype "unspecified"))
      (node (ref "D2") (pin "1") (pinfunction "1_1") (pintype "unspecified"))
      (node (ref "D3") (pin "2") (pinfunction "2_2") (pintype "unspecified"))
      (node (ref "D4") (pin "1") (pinfunction "1_1") (pintype "unspecified"))
      (node (ref "D5") (pin "1") (pinfunction "1_1") (pintype "unspecified"))
      (node (ref "L1") (pin "2") (pinfunction "2_2") (pintype "unspecified"))
      (node (ref "R4") (pin "1") (pinfunction "1_1") (pintype "input"))
      (node (ref "R5") (pin "1") (pinfunction "1_1") (pintype "input"))
      (node (ref "R6") (pin "1") (pinfunction "1_1") (pintype "input"))
      (node (ref "R7") (pin "1") (pinfunction "1_1") (pintype "input"))
      (node (ref "RJ1") (pin "3") (pinfunction "3_3") (pintype "unspecified"))
      (node (ref "RJ1") (pin "4") (pinfunction "4_4") (pintype "unspecified"))
      (node (ref "U2") (pin "1") (pinfunction "VDD2A_1") (pintype "unspecified"))
      (node (ref "U2") (pin "19") (pinfunction "VDD1A_19") (pintype "unspecified"))
    )
    (net (code "6") (name "DTR") (class "Default")
      (node (ref "PGM") (pin "1") (pinfunction "1_1") (pintype "unspecified"))
      (node (ref "Q3") (pin "2") (pinfunction "E_2") (pintype "unspecified"))
      (node (ref "R41") (pin "2") (pinfunction "2_2") (pintype "input"))
    )
    (net (code "7") (name "EGND") (class "Default")
      (node (ref "C11") (pin "1") (pinfunction "1_1") (pintype "input"))
      (node (ref "RJ1") (pin "GND1") (pinfunction "GND_GND1") (pintype "passive"))
      (node (ref "RJ1") (pin "GND2") (pinfunction "GND_GND2") (pintype "passive"))
    )
    (net (code "8") (name "EN") (class "Default")
      (node (ref "C36") (pin "1") (pinfunction "1_1") (pintype "input"))
      (node (ref "EN") (pin "3") (pinfunction "C_3") (pintype "unspecified"))
      (node (ref "Q4") (pin "3") (pinfunction "C_3") (pintype "unspecified"))
      (node (ref "R47") (pin "2") (pinfunction "2_2") (pintype "input"))
      (node (ref "U10") (pin "3") (pinfunction "EN_3") (pintype "unspecified"))
    )
    (net (code "9") (name "ESP_SCL") (class "Default")
      (node (ref "P14") (pin "15") (pinfunction "15_15") (pintype "input"))
      (node (ref "R45") (pin "2") (pinfunction "2_2") (pintype "input"))
      (node (ref "U10") (pin "9") (pinfunction "IO33_9") (pintype "unspecified"))
      (node (ref "U3") (pin "14") (pinfunction "SCL_14") (pintype "unspecified"))
      (node (ref "U8") (pin "14") (pinfunction "SCL_14") (pintype "unspecified"))
      (node (ref "U9") (pin "6") (pinfunction "SCL_6") (pintype "unspecified"))
    )
    (net (code "10") (name "ESP_SDA") (class "Default")
      (node (ref "P14") (pin "17") (pinfunction "17_17") (pintype "input"))
      (node (ref "R46") (pin "2") (pinfunction "2_2") (pintype "input"))
      (node (ref "U10") (pin "8") (pinfunction "IO32_8") (pintype "unspecified"))
      (node (ref "U3") (pin "15") (pinfunction "SDA_15") (pintype "unspecified"))
      (node (ref "U8") (pin "15") (pinfunction "SDA_15") (pintype "unspecified"))
      (node (ref "U9") (pin "5") (pinfunction "SDA_5") (pintype "unspecified"))
    )
    (net (code "11") (name "ETH_CRS_DV") (class "Default")
      (node (ref "R13") (pin "1") (pinfunction "1_1") (pintype "input"))
      (node (ref "U10") (pin "12") (pinfunction "IO27_12") (pintype "unspecified"))
    )
    (net (code "12") (name "ETH_MDC") (class "Default")
      (node (ref "U10") (pin "37") (pinfunction "IO23_37") (pintype "unspecified"))
      (node (ref "U2") (pin "13") (pinfunction "MDC_13") (pintype "unspecified"))
    )
    (net (code "13") (name "ETH_MDIO") (class "Default")
      (node (ref "R3") (pin "2") (pinfunction "2_2") (pintype "input"))
      (node (ref "U10") (pin "30") (pinfunction "IO18_30") (pintype "unspecified"))
      (node (ref "U2") (pin "12") (pinfunction "MDIO_12") (pintype "unspecified"))
    )
    (net (code "14") (name "ETH_REFCLK") (class "Default")
      (node (ref "R48") (pin "2") (pinfunction "2_2") (pintype "input"))
      (node (ref "RN1") (pin "1") (pinfunction "1_1") (pintype "input"))
      (node (ref "RN1") (pin "2") (pinfunction "2_2") (pintype "input"))
    )
    (net (code "15") (name "ETH_RXD+") (class "Default")
      (node (ref "R10") (pin "1") (pinfunction "1_1") (pintype "input"))
      (node (ref "U10") (pin "11") (pinfunction "IO26_11") (pintype "unspecified"))
    )
    (net (code "16") (name "ETH_RXD-") (class "Default")
      (node (ref "R12") (pin "1") (pinfunction "1_1") (pintype "input"))
      (node (ref "U10") (pin "10") (pinfunction "IO25_10") (pintype "unspecified"))
    )
    (net (code "17") (name "ETH_TXD+") (class "Default")
      (node (ref "U10") (pin "36") (pinfunction "IO22_36") (pintype "unspecified"))
      (node (ref "U2") (pin "18") (pinfunction "TXD1_18") (pintype "unspecified"))
    )
    (net (code "18") (name "ETH_TXD-") (class "Default")
      (node (ref "U10") (pin "31") (pinfunction "IO19_31") (pintype "unspecified"))
      (node (ref "U2") (pin "17") (pinfunction "TXD0_17") (pintype "unspecified"))
    )
    (net (code "19") (name "ETH_TXDEN") (class "Default")
      (node (ref "U10") (pin "33") (pinfunction "IO21_33") (pintype "unspecified"))
      (node (ref "U2") (pin "16") (pinfunction "TXEN_16") (pintype "unspecified"))
    )
    (net (code "20") (name "GND") (class "Default")
      (node (ref "BOOT") (pin "2") (pinfunction "B_2") (pintype "unspecified"))
      (node (ref "BT1") (pin "2") (pinfunction "2_2") (pintype "input"))
      (node (ref "C1") (pin "2") (pinfunction "2_2") (pintype "input"))
      (node (ref "C10") (pin "2") (pinfunction "2_2") (pintype "input"))
      (node (ref "C11") (pin "2") (pinfunction "2_2") (pintype "input"))
      (node (ref "C12") (pin "2") (pinfunction "2_2") (pintype "input"))
      (node (ref "C13") (pin "2") (pinfunction "2_2") (pintype "input"))
      (node (ref "C14") (pin "2") (pinfunction "2_2") (pintype "input"))
      (node (ref "C15") (pin "2") (pinfunction "2_2") (pintype "input"))
      (node (ref "C16") (pin "2") (pinfunction "2_2") (pintype "input"))
      (node (ref "C17") (pin "2") (pinfunction "2_2") (pintype "input"))
      (node (ref "C18") (pin "2") (pinfunction "2_2") (pintype "input"))
      (node (ref "C19") (pin "2") (pinfunction "2_2") (pintype "input"))
      (node (ref "C2") (pin "2") (pinfunction "2_2") (pintype "input"))
      (node (ref "C20") (pin "2") (pinfunction "2_2") (pintype "input"))
      (node (ref "C21") (pin "2") (pinfunction "2_2") (pintype "input"))
      (node (ref "C22") (pin "2") (pinfunction "2_2") (pintype "input"))
      (node (ref "C23") (pin "2") (pinfunction "2_2") (pintype "input"))
      (node (ref "C24") (pin "2") (pinfunction "2_2") (pintype "input"))
      (node (ref "C25") (pin "2") (pinfunction "2_2") (pintype "input"))
      (node (ref "C26") (pin "1") (pinfunction "1_1") (pintype "input"))
      (node (ref "C27") (pin "2") (pinfunction "2_2") (pintype "input"))
      (node (ref "C28") (pin "2") (pinfunction "2_2") (pintype "input"))
      (node (ref "C29") (pin "2") (pinfunction "2_2") (pintype "input"))
      (node (ref "C3") (pin "2") (pinfunction "2_2") (pintype "input"))
      (node (ref "C30") (pin "2") (pinfunction "2_2") (pintype "input"))
      (node (ref "C31") (pin "2") (pinfunction "2_2") (pintype "input"))
      (node (ref "C32") (pin "2") (pinfunction "2_2") (pintype "input"))
      (node (ref "C33") (pin "2") (pinfunction "2_2") (pintype "input"))
      (node (ref "C34") (pin "2") (pinfunction "2_2") (pintype "input"))
      (node (ref "C35") (pin "2") (pinfunction "2_2") (pintype "input"))
      (node (ref "C36") (pin "2") (pinfunction "2_2") (pintype "input"))
      (node (ref "C37") (pin "2") (pinfunction "2_2") (pintype "input"))
      (node (ref "C38") (pin "2") (pinfunction "2_2") (pintype "input"))
      (node (ref "C39") (pin "2") (pinfunction "2_2") (pintype "input"))
      (node (ref "C4") (pin "2") (pinfunction "2_2") (pintype "input"))
      (node (ref "C40") (pin "2") (pinfunction "2_2") (pintype "input"))
      (node (ref "C5") (pin "2") (pinfunction "2_2") (pintype "input"))
      (node (ref "C6") (pin "2") (pinfunction "2_2") (pintype "input"))
      (node (ref "C7") (pin "2") (pinfunction "2_2") (pintype "input"))
      (node (ref "C8") (pin "2") (pinfunction "2_2") (pintype "input"))
      (node (ref "C9") (pin "2") (pinfunction "2_2") (pintype "unspecified"))
      (node (ref "D10") (pin "2") (pinfunction "2_2") (pintype "unspecified"))
      (node (ref "D11") (pin "2") (pinfunction "A_2") (pintype "unspecified"))
      (node (ref "D12") (pin "2") (pinfunction "A_2") (pintype "unspecified"))
      (node (ref "D13") (pin "2") (pinfunction "2_2") (pintype "unspecified"))
      (node (ref "D18") (pin "2") (pinfunction "2_2") (pintype "unspecified"))
      (node (ref "D19") (pin "2") (pinfunction "A_2") (pintype "unspecified"))
      (node (ref "D21") (pin "2") (pinfunction "A_2") (pintype "unspecified"))
      (node (ref "D26") (pin "2") (pinfunction "2_2") (pintype "unspecified"))
      (node (ref "D27") (pin "2") (pinfunction "2_2") (pintype "unspecified"))
      (node (ref "D28") (pin "2") (pinfunction "A_2") (pintype "unspecified"))
      (node (ref "D29") (pin "2") (pinfunction "A_2") (pintype "unspecified"))
      (node (ref "D30") (pin "2") (pinfunction "2_2") (pintype "unspecified"))
      (node (ref "D31") (pin "2") (pinfunction "2_2") (pintype "unspecified"))
      (node (ref "D32") (pin "2") (pinfunction "A_2") (pintype "unspecified"))
      (node (ref "D33") (pin "2") (pinfunction "2_2") (pintype "unspecified"))
      (node (ref "D34") (pin "2") (pinfunction "2_2") (pintype "unspecified"))
      (node (ref "D35") (pin "2") (pinfunction "A_2") (pintype "unspecified"))
      (node (ref "D36") (pin "2") (pinfunction "A_2") (pintype "unspecified"))
      (node (ref "D37") (pin "2") (pinfunction "2_2") (pintype "unspecified"))
      (node (ref "D42") (pin "2") (pinfunction "A_2") (pintype "unspecified"))
      (node (ref "D43") (pin "2") (pinfunction "2_2") (pintype "unspecified"))
      (node (ref "D44") (pin "2") (pinfunction "+_2") (pintype "unspecified"))
      (node (ref "D5") (pin "2") (pinfunction "2_2") (pintype "unspecified"))
      (node (ref "D6") (pin "2") (pinfunction "2_2") (pintype "unspecified"))
      (node (ref "D8") (pin "2") (pinfunction "A_2") (pintype "unspecified"))
      (node (ref "D9") (pin "2") (pinfunction "2_2") (pintype "unspecified"))
      (node (ref "EN") (pin "2") (pinfunction "B_2") (pintype "unspecified"))
      (node (ref "F11") (pin "2") (pinfunction "2_2") (pintype "unspecified"))
      (node (ref "F12") (pin "2") (pinfunction "2_2") (pintype "unspecified"))
      (node (ref "F13") (pin "2") (pinfunction "2_2") (pintype "unspecified"))
      (node (ref "F14") (pin "2") (pinfunction "2_2") (pintype "unspecified"))
      (node (ref "F5") (pin "2") (pinfunction "2_2") (pintype "unspecified"))
      (node (ref "F6") (pin "2") (pinfunction "2_2") (pintype "unspecified"))
      (node (ref "F7") (pin "2") (pinfunction "2_2") (pintype "unspecified"))
      (node (ref "F8") (pin "2") (pinfunction "2_2") (pintype "unspecified"))
      (node (ref "LED1") (pin "2") (pinfunction "C_2") (pintype "input"))
      (node (ref "P1") (pin "2") (pinfunction "2_2") (pintype "unspecified"))
      (node (ref "P12") (pin "2") (pinfunction "2_2") (pintype "unspecified"))
      (node (ref "P14") (pin "1") (pinfunction "1_1") (pintype "input"))
      (node (ref "P14") (pin "12") (pinfunction "12_12") (pintype "input"))
      (node (ref "P14") (pin "18") (pinfunction "18_18") (pintype "input"))
      (node (ref "P14") (pin "19") (pinfunction "19_19") (pintype "input"))
      (node (ref "P14") (pin "2") (pinfunction "2_2") (pintype "input"))
      (node (ref "P14") (pin "20") (pinfunction "20_20") (pintype "input"))
      (node (ref "P14") (pin "3") (pinfunction "3_3") (pintype "input"))
      (node (ref "P14") (pin "6") (pinfunction "6_6") (pintype "input"))
      (node (ref "P15") (pin "1") (pinfunction "1_1") (pintype "unspecified"))
      (node (ref "P16") (pin "1") (pinfunction "1_1") (pintype "unspecified"))
      (node (ref "P2") (pin "2") (pinfunction "2_2") (pintype "unspecified"))
      (node (ref "P7") (pin "2") (pinfunction "2_2") (pintype "unspecified"))
      (node (ref "PGM") (pin "6") (pinfunction "6_6") (pintype "unspecified"))
      (node (ref "Q5") (pin "2") (pinfunction "S_2") (pintype "unspecified"))
      (node (ref "R17") (pin "2") (pinfunction "2_2") (pintype "input"))
      (node (ref "R23") (pin "2") (pinfunction "2_2") (pintype "input"))
      (node (ref "R24") (pin "2") (pinfunction "2_2") (pintype "input"))
      (node (ref "R25") (pin "2") (pinfunction "2_2") (pintype "input"))
      (node (ref "R26") (pin "2") (pinfunction "2_2") (pintype "input"))
      (node (ref "R27") (pin "2") (pinfunction "2_2") (pintype "input"))
      (node (ref "R28") (pin "2") (pinfunction "2_2") (pintype "input"))
      (node (ref "R29") (pin "2") (pinfunction "2_2") (pintype "input"))
      (node (ref "R30") (pin "2") (pinfunction "2_2") (pintype "input"))
      (node (ref "R31") (pin "2") (pinfunction "2_2") (pintype "input"))
      (node (ref "R35") (pin "1") (pinfunction "1_1") (pintype "input"))
      (node (ref "R49") (pin "2") (pinfunction "2_2") (pintype "input"))
      (node (ref "R52") (pin "2") (pinfunction "2_2") (pintype "input"))
      (node (ref "R9") (pin "2") (pinfunction "2_2") (pintype "input"))
      (node (ref "RF1") (pin "2") (pinfunction "GND_2") (pintype "unspecified"))
      (node (ref "RF1") (pin "3") (pinfunction "GND_3") (pintype "unspecified"))
      (node (ref "RF1") (pin "4") (pinfunction "GND_4") (pintype "unspecified"))
      (node (ref "RF1") (pin "5") (pinfunction "GND_5") (pintype "unspecified"))
      (node (ref "U1") (pin "7") (pinfunction "-VDC_7") (pintype "unspecified"))
      (node (ref "U1") (pin "8") (pinfunction "-VDC_8") (pintype "unspecified"))
      (node (ref "U10") (pin "1") (pinfunction "GND_1") (pintype "unspecified"))
      (node (ref "U10") (pin "15") (pinfunction "GND_15") (pintype "unspecified"))
      (node (ref "U10") (pin "38") (pinfunction "GND_38") (pintype "unspecified"))
      (node (ref "U10") (pin "39") (pinfunction "GND_39") (pintype "unspecified"))
      (node (ref "U11") (pin "3") (pinfunction "Gnd_3") (pintype "unspecified"))
      (node (ref "U11") (pin "5") (pinfunction "ON#/OFF_5") (pintype "unspecified"))
      (node (ref "U11") (pin "6") (pinfunction "TAB_6") (pintype "unspecified"))
      (node (ref "U2") (pin "25") (pinfunction "EP_25") (pintype "unspecified"))
      (node (ref "U3") (pin "3") (pinfunction "A2_3") (pintype "unspecified"))
      (node (ref "U3") (pin "8") (pinfunction "VSS_8") (pintype "unspecified"))
      (node (ref "U4") (pin "10") (pinfunction "GND_10") (pintype "unspecified"))
      (node (ref "U5") (pin "2") (pinfunction "GND_2") (pintype "passive"))
      (node (ref "U6") (pin "3") (pinfunction "Ground_3") (pintype "unspecified"))
      (node (ref "U7") (pin "2") (pinfunction "GND_2") (pintype "passive"))
      (node (ref "U8") (pin "2") (pinfunction "A1_2") (pintype "unspecified"))
      (node (ref "U8") (pin "8") (pinfunction "VSS_8") (pintype "unspecified"))
      (node (ref "U9") (pin "4") (pinfunction "GND_4") (pintype "unspecified"))
      (node (ref "X1") (pin "2") (pinfunction "GND_2") (pintype "unspecified"))
    )
    (net (code "21") (name "GPIO0") (class "Default")
      (node (ref "BOOT") (pin "3") (pinfunction "C_3") (pintype "unspecified"))
      (node (ref "Q3") (pin "3") (pinfunction "C_3") (pintype "unspecified"))
      (node (ref "R48") (pin "1") (pinfunction "1_1") (pintype "input"))
      (node (ref "U10") (pin "25") (pinfunction "IO0_25") (pintype "unspecified"))
    )
    (net (code "22") (name "GPIO4") (class "Default")
      (node (ref "D33") (pin "1") (pinfunction "1_1") (pintype "unspecified"))
      (node (ref "D35") (pin "1") (pinfunction "C_1") (pintype "unspecified"))
      (node (ref "F17") (pin "1") (pinfunction "1_1") (pintype "unspecified"))
      (node (ref "IO2") (pin "1") (pinfunction "1_1") (pintype "unspecified"))
      (node (ref "P14") (pin "8") (pinfunction "8_8") (pintype "input"))
      (node (ref "U10") (pin "26") (pinfunction "IO4_26") (pintype "unspecified"))
    )
    (net (code "23") (name "GPIO5") (class "Default")
      (node (ref "D34") (pin "1") (pinfunction "1_1") (pintype "unspecified"))
      (node (ref "D36") (pin "1") (pinfunction "C_1") (pintype "unspecified"))
      (node (ref "F18") (pin "1") (pinfunction "1_1") (pintype "unspecified"))
      (node (ref "IO1") (pin "1") (pinfunction "1_1") (pintype "unspecified"))
      (node (ref "P14") (pin "10") (pinfunction "10_10") (pintype "input"))
      (node (ref "U10") (pin "29") (pinfunction "IO5_29") (pintype "unspecified"))
    )
    (net (code "24") (name "INPUT_0") (class "Default")
      (node (ref "C12") (pin "1") (pinfunction "1_1") (pintype "input"))
      (node (ref "D8") (pin "1") (pinfunction "C_1") (pintype "unspecified"))
      (node (ref "D9") (pin "1") (pinfunction "1_1") (pintype "unspecified"))
      (node (ref "F1") (pin "2") (pinfunction "2_2") (pintype "unspecified"))
      (node (ref "R14") (pin "2") (pinfunction "2_2") (pintype "input"))
      (node (ref "U8") (pin "4") (pinfunction "P0_4") (pintype "unspecified"))
    )
    (net (code "25") (name "INPUT_1") (class "Default")
      (node (ref "C15") (pin "1") (pinfunction "1_1") (pintype "input"))
      (node (ref "D10") (pin "1") (pinfunction "1_1") (pintype "unspecified"))
      (node (ref "D11") (pin "1") (pinfunction "C_1") (pintype "unspecified"))
      (node (ref "F2") (pin "1") (pinfunction "1_1") (pintype "unspecified"))
      (node (ref "R15") (pin "2") (pinfunction "2_2") (pintype "input"))
      (node (ref "U8") (pin "5") (pinfunction "P1_5") (pintype "unspecified"))
    )
    (net (code "26") (name "INPUT_2") (class "Default")
      (node (ref "C17") (pin "1") (pinfunction "1_1") (pintype "input"))
      (node (ref "D12") (pin "1") (pinfunction "C_1") (pintype "unspecified"))
      (node (ref "D13") (pin "1") (pinfunction "1_1") (pintype "unspecified"))
      (node (ref "F3") (pin "2") (pinfunction "2_2") (pintype "unspecified"))
      (node (ref "R18") (pin "2") (pinfunction "2_2") (pintype "input"))
      (node (ref "U8") (pin "6") (pinfunction "P2_6") (pintype "unspecified"))
    )
    (net (code "27") (name "INPUT_3") (class "Default")
      (node (ref "C18") (pin "1") (pinfunction "1_1") (pintype "input"))
      (node (ref "D18") (pin "1") (pinfunction "1_1") (pintype "unspecified"))
      (node (ref "D19") (pin "1") (pinfunction "C_1") (pintype "unspecified"))
      (node (ref "F4") (pin "1") (pinfunction "1_1") (pintype "unspecified"))
      (node (ref "R19") (pin "2") (pinfunction "2_2") (pintype "input"))
      (node (ref "U8") (pin "7") (pinfunction "P3_7") (pintype "unspecified"))
    )
    (net (code "28") (name "INPUT_4") (class "Default")
      (node (ref "C21") (pin "1") (pinfunction "1_1") (pintype "input"))
      (node (ref "D21") (pin "1") (pinfunction "C_1") (pintype "unspecified"))
      (node (ref "D26") (pin "1") (pinfunction "1_1") (pintype "unspecified"))
      (node (ref "F9") (pin "2") (pinfunction "2_2") (pintype "unspecified"))
      (node (ref "R21") (pin "2") (pinfunction "2_2") (pintype "input"))
      (node (ref "U8") (pin "9") (pinfunction "P4_9") (pintype "unspecified"))
    )
    (net (code "29") (name "INPUT_5") (class "Default")
      (node (ref "C25") (pin "1") (pinfunction "1_1") (pintype "input"))
      (node (ref "D27") (pin "1") (pinfunction "1_1") (pintype "unspecified"))
      (node (ref "D28") (pin "1") (pinfunction "C_1") (pintype "unspecified"))
      (node (ref "F10") (pin "1") (pinfunction "1_1") (pintype "unspecified"))
      (node (ref "R34") (pin "2") (pinfunction "2_2") (pintype "input"))
      (node (ref "U8") (pin "10") (pinfunction "P5_10") (pintype "unspecified"))
    )
    (net (code "30") (name "INPUT_6") (class "Default")
      (node (ref "C27") (pin "1") (pinfunction "1_1") (pintype "input"))
      (node (ref "D29") (pin "1") (pinfunction "C_1") (pintype "unspecified"))
      (node (ref "D30") (pin "1") (pinfunction "1_1") (pintype "unspecified"))
      (node (ref "F15") (pin "2") (pinfunction "2_2") (pintype "unspecified"))
      (node (ref "R36") (pin "2") (pinfunction "2_2") (pintype "input"))
      (node (ref "U8") (pin "11") (pinfunction "P6_11") (pintype "unspecified"))
    )
    (net (code "31") (name "INPUT_7") (class "Default")
      (node (ref "C28") (pin "1") (pinfunction "1_1") (pintype "input"))
      (node (ref "D31") (pin "1") (pinfunction "1_1") (pintype "unspecified"))
      (node (ref "D32") (pin "1") (pinfunction "C_1") (pintype "unspecified"))
      (node (ref "F16") (pin "1") (pinfunction "1_1") (pintype "unspecified"))
      (node (ref "R37") (pin "2") (pinfunction "2_2") (pintype "input"))
      (node (ref "U8") (pin "12") (pinfunction "P7_12") (pintype "unspecified"))
    )
    (net (code "32") (name "INT") (class "Default")
      (node (ref "INT") (pin "2") (pinfunction "2_2") (pintype "unspecified"))
      (node (ref "P14") (pin "9") (pinfunction "9_9") (pintype "input"))
      (node (ref "U10") (pin "16") (pinfunction "IO13_16") (pintype "unspecified"))
    )
    (net (code "33") (name "LED_G") (class "Default")
      (node (ref "R11") (pin "2") (pinfunction "2_2") (pintype "input"))
      (node (ref "U2") (pin "3") (pinfunction "LED1/REGOFF_3") (pintype "unspecified"))
    )
    (net (code "34") (name "LED_Y") (class "Default")
      (node (ref "R8") (pin "2") (pinfunction "2_2") (pintype "input"))
      (node (ref "U2") (pin "2") (pinfunction "LED2/nINTSEL_2") (pintype "unspecified"))
    )
    (net (code "35") (name "Net-(D14-+)") (class "Default")
      (node (ref "D14") (pin "2") (pinfunction "+_2") (pintype "unspecified"))
      (node (ref "F5") (pin "1") (pinfunction "1_1") (pintype "unspecified"))
      (node (ref "RELAY1") (pin "4") (pinfunction "4_4") (pintype "input"))
    )
    (net (code "36") (name "Net-(D15-+)") (class "Default")
      (node (ref "D15") (pin "2") (pinfunction "+_2") (pintype "unspecified"))
      (node (ref "F6") (pin "1") (pinfunction "1_1") (pintype "unspecified"))
      (node (ref "RELAY2") (pin "4") (pinfunction "4_4") (pintype "input"))
    )
    (net (code "37") (name "Net-(D16-+)") (class "Default")
      (node (ref "D16") (pin "2") (pinfunction "+_2") (pintype "unspecified"))
      (node (ref "F7") (pin "1") (pinfunction "1_1") (pintype "unspecified"))
      (node (ref "RELAY3") (pin "4") (pinfunction "4_4") (pintype "input"))
    )
    (net (code "38") (name "Net-(D17-+)") (class "Default")
      (node (ref "D17") (pin "2") (pinfunction "+_2") (pintype "unspecified"))
      (node (ref "F8") (pin "1") (pinfunction "1_1") (pintype "unspecified"))
      (node (ref "RELAY4") (pin "4") (pinfunction "4_4") (pintype "input"))
    )
    (net (code "39") (name "Net-(D20-A)") (class "Default")
      (node (ref "D20") (pin "2") (pinfunction "A_2") (pintype "unspecified"))
      (node (ref "Q1") (pin "1") (pinfunction "G_1") (pintype "unspecified"))
      (node (ref "Q2") (pin "3") (pinfunction "C_3") (pintype "unspecified"))
      (node (ref "R22") (pin "2") (pinfunction "2_2") (pintype "input"))
    )
    (net (code "40") (name "Net-(D22-+)") (class "Default")
      (node (ref "D22") (pin "2") (pinfunction "+_2") (pintype "unspecified"))
      (node (ref "F11") (pin "1") (pinfunction "1_1") (pintype "unspecified"))
      (node (ref "RELAY5") (pin "4") (pinfunction "4_4") (pintype "input"))
    )
    (net (code "41") (name "Net-(D23-+)") (class "Default")
      (node (ref "D23") (pin "2") (pinfunction "+_2") (pintype "unspecified"))
      (node (ref "F12") (pin "1") (pinfunction "1_1") (pintype "unspecified"))
      (node (ref "RELAY6") (pin "4") (pinfunction "4_4") (pintype "input"))
    )
    (net (code "42") (name "Net-(D24-+)") (class "Default")
      (node (ref "D24") (pin "2") (pinfunction "+_2") (pintype "unspecified"))
      (node (ref "F13") (pin "1") (pinfunction "1_1") (pintype "unspecified"))
      (node (ref "RELAY7") (pin "4") (pinfunction "4_4") (pintype "input"))
    )
    (net (code "43") (name "Net-(D25-+)") (class "Default")
      (node (ref "D25") (pin "2") (pinfunction "+_2") (pintype "unspecified"))
      (node (ref "F14") (pin "1") (pinfunction "1_1") (pintype "unspecified"))
      (node (ref "RELAY8") (pin "4") (pinfunction "4_4") (pintype "input"))
    )
    (net (code "44") (name "Net-(D38-K)") (class "Default")
      (node (ref "D38") (pin "1") (pinfunction "K_1") (pintype "unspecified"))
      (node (ref "D39") (pin "1") (pinfunction "K_1") (pintype "unspecified"))
      (node (ref "F20") (pin "1") (pinfunction "1_1") (pintype "unspecified"))
    )
    (net (code "45") (name "Net-(D39-A)") (class "Default")
      (node (ref "D39") (pin "2") (pinfunction "A_2") (pintype "unspecified"))
      (node (ref "D41") (pin "2") (pinfunction "A_2") (pintype "unspecified"))
      (node (ref "D43") (pin "1") (pinfunction "1_1") (pintype "unspecified"))
      (node (ref "P16") (pin "2") (pinfunction "2_2") (pintype "unspecified"))
    )
    (net (code "46") (name "Net-(D44--)") (class "Default")
      (node (ref "D44") (pin "1") (pinfunction "-_1") (pintype "unspecified"))
      (node (ref "L2") (pin "1") (pinfunction "1_1") (pintype "unspecified"))
      (node (ref "U11") (pin "2") (pinfunction "Output_2") (pintype "unspecified"))
    )
    (net (code "47") (name "Net-(DRV-Pad2)") (class "Default")
      (node (ref "DRV") (pin "2") (pinfunction "2_2") (pintype "unspecified"))
      (node (ref "R33") (pin "2") (pinfunction "2_2") (pintype "input"))
      (node (ref "R35") (pin "2") (pinfunction "2_2") (pintype "input"))
    )
    (net (code "48") (name "Net-(F1-Pad1)") (class "Default")
      (node (ref "F1") (pin "1") (pinfunction "1_1") (pintype "unspecified"))
      (node (ref "P1") (pin "1") (pinfunction "1_1") (pintype "unspecified"))
    )
    (net (code "49") (name "Net-(F2-Pad2)") (class "Default")
      (node (ref "F2") (pin "2") (pinfunction "2_2") (pintype "unspecified"))
      (node (ref "P1") (pin "3") (pinfunction "3_3") (pintype "unspecified"))
    )
    (net (code "50") (name "Net-(F3-Pad1)") (class "Default")
      (node (ref "F3") (pin "1") (pinfunction "1_1") (pintype "unspecified"))
      (node (ref "P2") (pin "1") (pinfunction "1_1") (pintype "unspecified"))
    )
    (net (code "51") (name "Net-(F4-Pad2)") (class "Default")
      (node (ref "F4") (pin "2") (pinfunction "2_2") (pintype "unspecified"))
      (node (ref "P2") (pin "3") (pinfunction "3_3") (pintype "unspecified"))
    )
    (net (code "52") (name "Net-(F9-Pad1)") (class "Default")
      (node (ref "F9") (pin "1") (pinfunction "1_1") (pintype "unspecified"))
      (node (ref "P7") (pin "1") (pinfunction "1_1") (pintype "unspecified"))
    )
    (net (code "53") (name "Net-(F10-Pad2)") (class "Default")
      (node (ref "F10") (pin "2") (pinfunction "2_2") (pintype "unspecified"))
      (node (ref "P7") (pin "3") (pinfunction "3_3") (pintype "unspecified"))
    )
    (net (code "54") (name "Net-(F15-Pad1)") (class "Default")
      (node (ref "F15") (pin "1") (pinfunction "1_1") (pintype "unspecified"))
      (node (ref "P12") (pin "1") (pinfunction "1_1") (pintype "unspecified"))
    )
    (net (code "55") (name "Net-(F16-Pad2)") (class "Default")
      (node (ref "F16") (pin "2") (pinfunction "2_2") (pintype "unspecified"))
      (node (ref "P12") (pin "3") (pinfunction "3_3") (pintype "unspecified"))
    )
    (net (code "56") (name "Net-(F17-Pad2)") (class "Default")
      (node (ref "F17") (pin "2") (pinfunction "2_2") (pintype "unspecified"))
      (node (ref "P13") (pin "1") (pinfunction "1_1") (pintype "unspecified"))
    )
    (net (code "57") (name "Net-(F18-Pad2)") (class "Default")
      (node (ref "F18") (pin "2") (pinfunction "2_2") (pintype "unspecified"))
      (node (ref "P13") (pin "2") (pinfunction "2_2") (pintype "unspecified"))
    )
    (net (code "58") (name "Net-(F19-Pad1)") (class "Default")
      (node (ref "F19") (pin "1") (pinfunction "1_1") (pintype "unspecified"))
      (node (ref "P15") (pin "2") (pinfunction "2_2") (pintype "unspecified"))
    )
    (net (code "59") (name "Net-(IO1-Pad2)") (class "Default")
      (node (ref "IO1") (pin "2") (pinfunction "2_2") (pintype "unspecified"))
      (node (ref "R43") (pin "2") (pinfunction "2_2") (pintype "input"))
    )
    (net (code "60") (name "Net-(IO2-Pad2)") (class "Default")
      (node (ref "IO2") (pin "2") (pinfunction "2_2") (pintype "unspecified"))
      (node (ref "R44") (pin "2") (pinfunction "2_2") (pintype "input"))
    )
    (net (code "61") (name "Net-(LED1-A)") (class "Default")
      (node (ref "LED1") (pin "1") (pinfunction "A_1") (pintype "input"))
      (node (ref "R20") (pin "1") (pinfunction "1_1") (pintype "input"))
    )
    (net (code "62") (name "Net-(LED2-C)") (class "Default")
      (node (ref "LED2") (pin "2") (pinfunction "C_2") (pintype "input"))
      (node (ref "R27") (pin "1") (pinfunction "1_1") (pintype "input"))
    )
    (net (code "63") (name "Net-(LED3-C)") (class "Default")
      (node (ref "LED3") (pin "2") (pinfunction "C_2") (pintype "input"))
      (node (ref "R31") (pin "1") (pinfunction "1_1") (pintype "input"))
    )
    (net (code "64") (name "Net-(LED4-C)") (class "Default")
      (node (ref "LED4") (pin "2") (pinfunction "C_2") (pintype "input"))
      (node (ref "R26") (pin "1") (pinfunction "1_1") (pintype "input"))
    )
    (net (code "65") (name "Net-(LED5-C)") (class "Default")
      (node (ref "LED5") (pin "2") (pinfunction "C_2") (pintype "input"))
      (node (ref "R30") (pin "1") (pinfunction "1_1") (pintype "input"))
    )
    (net (code "66") (name "Net-(LED6-C)") (class "Default")
      (node (ref "LED6") (pin "2") (pinfunction "C_2") (pintype "input"))
      (node (ref "R25") (pin "1") (pinfunction "1_1") (pintype "input"))
    )
    (net (code "67") (name "Net-(LED7-C)") (class "Default")
      (node (ref "LED7") (pin "2") (pinfunction "C_2") (pintype "input"))
      (node (ref "R29") (pin "1") (pinfunction "1_1") (pintype "input"))
    )
    (net (code "68") (name "Net-(LED8-C)") (class "Default")
      (node (ref "LED8") (pin "2") (pinfunction "C_2") (pintype "input"))
      (node (ref "R24") (pin "1") (pinfunction "1_1") (pintype "input"))
    )
    (net (code "69") (name "Net-(LED9-C)") (class "Default")
      (node (ref "LED9") (pin "2") (pinfunction "C_2") (pintype "input"))
      (node (ref "R28") (pin "1") (pinfunction "1_1") (pintype "input"))
    )
    (net (code "70") (name "Net-(LED10-A)") (class "Default")
      (node (ref "LED10") (pin "1") (pinfunction "A_1") (pintype "input"))
      (node (ref "R51") (pin "2") (pinfunction "2_2") (pintype "input"))
    )
    (net (code "71") (name "Net-(LED10-C)") (class "Default")
      (node (ref "LED10") (pin "2") (pinfunction "C_2") (pintype "input"))
      (node (ref "Q5") (pin "3") (pinfunction "D_3") (pintype "unspecified"))
    )
    (net (code "72") (name "Net-(LED11-C)") (class "Default")
      (node (ref "LED11") (pin "2") (pinfunction "C_2") (pintype "input"))
      (node (ref "R52") (pin "1") (pinfunction "1_1") (pintype "input"))
    )
    (net (code "73") (name "Net-(P3-Pad1)") (class "Default")
      (node (ref "P3") (pin "1") (pinfunction "1_1") (pintype "unspecified"))
      (node (ref "RELAY1") (pin "2") (pinfunction "2_2") (pintype "input"))
    )
    (net (code "74") (name "Net-(P3-Pad2)") (class "Default")
      (node (ref "P3") (pin "2") (pinfunction "2_2") (pintype "unspecified"))
      (node (ref "RELAY1") (pin "5") (pinfunction "5_5") (pintype "input"))
    )
    (net (code "75") (name "Net-(P3-Pad3)") (class "Default")
      (node (ref "P3") (pin "3") (pinfunction "3_3") (pintype "unspecified"))
      (node (ref "RELAY1") (pin "3") (pinfunction "3_3") (pintype "input"))
    )
    (net (code "76") (name "Net-(P4-Pad1)") (class "Default")
      (node (ref "P4") (pin "1") (pinfunction "1_1") (pintype "unspecified"))
      (node (ref "RELAY2") (pin "2") (pinfunction "2_2") (pintype "input"))
    )
    (net (code "77") (name "Net-(P4-Pad2)") (class "Default")
      (node (ref "P4") (pin "2") (pinfunction "2_2") (pintype "unspecified"))
      (node (ref "RELAY2") (pin "5") (pinfunction "5_5") (pintype "input"))
    )
    (net (code "78") (name "Net-(P4-Pad3)") (class "Default")
      (node (ref "P4") (pin "3") (pinfunction "3_3") (pintype "unspecified"))
      (node (ref "RELAY2") (pin "3") (pinfunction "3_3") (pintype "input"))
    )
    (net (code "79") (name "Net-(P5-Pad1)") (class "Default")
      (node (ref "P5") (pin "1") (pinfunction "1_1") (pintype "unspecified"))
      (node (ref "RELAY3") (pin "2") (pinfunction "2_2") (pintype "input"))
    )
    (net (code "80") (name "Net-(P5-Pad2)") (class "Default")
      (node (ref "P5") (pin "2") (pinfunction "2_2") (pintype "unspecified"))
      (node (ref "RELAY3") (pin "5") (pinfunction "5_5") (pintype "input"))
    )
    (net (code "81") (name "Net-(P5-Pad3)") (class "Default")
      (node (ref "P5") (pin "3") (pinfunction "3_3") (pintype "unspecified"))
      (node (ref "RELAY3") (pin "3") (pinfunction "3_3") (pintype "input"))
    )
    (net (code "82") (name "Net-(P6-Pad1)") (class "Default")
      (node (ref "P6") (pin "1") (pinfunction "1_1") (pintype "unspecified"))
      (node (ref "RELAY4") (pin "2") (pinfunction "2_2") (pintype "input"))
    )
    (net (code "83") (name "Net-(P6-Pad2)") (class "Default")
      (node (ref "P6") (pin "2") (pinfunction "2_2") (pintype "unspecified"))
      (node (ref "RELAY4") (pin "5") (pinfunction "5_5") (pintype "input"))
    )
    (net (code "84") (name "Net-(P6-Pad3)") (class "Default")
      (node (ref "P6") (pin "3") (pinfunction "3_3") (pintype "unspecified"))
      (node (ref "RELAY4") (pin "3") (pinfunction "3_3") (pintype "input"))
    )
    (net (code "85") (name "Net-(P8-Pad1)") (class "Default")
      (node (ref "P8") (pin "1") (pinfunction "1_1") (pintype "unspecified"))
      (node (ref "RELAY5") (pin "2") (pinfunction "2_2") (pintype "input"))
    )
    (net (code "86") (name "Net-(P8-Pad2)") (class "Default")
      (node (ref "P8") (pin "2") (pinfunction "2_2") (pintype "unspecified"))
      (node (ref "RELAY5") (pin "5") (pinfunction "5_5") (pintype "input"))
    )
    (net (code "87") (name "Net-(P8-Pad3)") (class "Default")
      (node (ref "P8") (pin "3") (pinfunction "3_3") (pintype "unspecified"))
      (node (ref "RELAY5") (pin "3") (pinfunction "3_3") (pintype "input"))
    )
    (net (code "88") (name "Net-(P9-Pad1)") (class "Default")
      (node (ref "P9") (pin "1") (pinfunction "1_1") (pintype "unspecified"))
      (node (ref "RELAY6") (pin "2") (pinfunction "2_2") (pintype "input"))
    )
    (net (code "89") (name "Net-(P9-Pad2)") (class "Default")
      (node (ref "P9") (pin "2") (pinfunction "2_2") (pintype "unspecified"))
      (node (ref "RELAY6") (pin "5") (pinfunction "5_5") (pintype "input"))
    )
    (net (code "90") (name "Net-(P9-Pad3)") (class "Default")
      (node (ref "P9") (pin "3") (pinfunction "3_3") (pintype "unspecified"))
      (node (ref "RELAY6") (pin "3") (pinfunction "3_3") (pintype "input"))
    )
    (net (code "91") (name "Net-(P10-Pad1)") (class "Default")
      (node (ref "P10") (pin "1") (pinfunction "1_1") (pintype "unspecified"))
      (node (ref "RELAY7") (pin "2") (pinfunction "2_2") (pintype "input"))
    )
    (net (code "92") (name "Net-(P10-Pad2)") (class "Default")
      (node (ref "P10") (pin "2") (pinfunction "2_2") (pintype "unspecified"))
      (node (ref "RELAY7") (pin "5") (pinfunction "5_5") (pintype "input"))
    )
    (net (code "93") (name "Net-(P10-Pad3)") (class "Default")
      (node (ref "P10") (pin "3") (pinfunction "3_3") (pintype "unspecified"))
      (node (ref "RELAY7") (pin "3") (pinfunction "3_3") (pintype "input"))
    )
    (net (code "94") (name "Net-(P11-Pad1)") (class "Default")
      (node (ref "P11") (pin "1") (pinfunction "1_1") (pintype "unspecified"))
      (node (ref "RELAY8") (pin "2") (pinfunction "2_2") (pintype "input"))
    )
    (net (code "95") (name "Net-(P11-Pad2)") (class "Default")
      (node (ref "P11") (pin "2") (pinfunction "2_2") (pintype "unspecified"))
      (node (ref "RELAY8") (pin "5") (pinfunction "5_5") (pintype "input"))
    )
    (net (code "96") (name "Net-(P11-Pad3)") (class "Default")
      (node (ref "P11") (pin "3") (pinfunction "3_3") (pintype "unspecified"))
      (node (ref "RELAY8") (pin "3") (pinfunction "3_3") (pintype "input"))
    )
    (net (code "97") (name "Net-(PHY-Pad1)") (class "Default")
      (node (ref "PHY") (pin "1") (pinfunction "1_1") (pintype "unspecified"))
      (node (ref "R16") (pin "1") (pinfunction "1_1") (pintype "input"))
    )
    (net (code "98") (name "Net-(Q1-D)") (class "Default")
      (node (ref "C19") (pin "1") (pinfunction "1_1") (pintype "input"))
      (node (ref "C20") (pin "1") (pinfunction "1_1") (pintype "input"))
      (node (ref "Q1") (pin "3") (pinfunction "D_3") (pintype "unspecified"))
      (node (ref "R20") (pin "2") (pinfunction "2_2") (pintype "input"))
      (node (ref "U4") (pin "9") (pinfunction "VCC_9") (pintype "unspecified"))
    )
    (net (code "99") (name "Net-(Q2-B)") (class "Default")
      (node (ref "C22") (pin "1") (pinfunction "1_1") (pintype "input"))
      (node (ref "Q2") (pin "1") (pinfunction "B_1") (pintype "unspecified"))
      (node (ref "R33") (pin "1") (pinfunction "1_1") (pintype "input"))
    )
    (net (code "100") (name "Net-(Q2-E)") (class "Default")
      (node (ref "Q2") (pin "2") (pinfunction "E_2") (pintype "unspecified"))
      (node (ref "R23") (pin "1") (pinfunction "1_1") (pintype "input"))
    )
    (net (code "101") (name "Net-(Q3-B)") (class "Default")
      (node (ref "Q3") (pin "1") (pinfunction "B_1") (pintype "unspecified"))
      (node (ref "R39") (pin "1") (pinfunction "1_1") (pintype "input"))
    )
    (net (code "102") (name "Net-(Q4-B)") (class "Default")
      (node (ref "Q4") (pin "1") (pinfunction "B_1") (pintype "unspecified"))
      (node (ref "R41") (pin "1") (pinfunction "1_1") (pintype "input"))
    )
    (net (code "103") (name "Net-(Q5-G)") (class "Default")
      (node (ref "Q5") (pin "1") (pinfunction "G_1") (pintype "unspecified"))
      (node (ref "R50") (pin "2") (pinfunction "2_2") (pintype "input"))
    )
    (net (code "104") (name "Net-(R8-Pad1)") (class "Default")
      (node (ref "R8") (pin "1") (pinfunction "1_1") (pintype "input"))
      (node (ref "RJ1") (pin "12") (pinfunction "12_12") (pintype "unspecified"))
    )
    (net (code "105") (name "Net-(R11-Pad1)") (class "Default")
      (node (ref "R11") (pin "1") (pinfunction "1_1") (pintype "input"))
      (node (ref "RJ1") (pin "14") (pinfunction "14_14") (pintype "unspecified"))
    )
    (net (code "106") (name "Net-(R42-Pad2)") (class "Default")
      (node (ref "R42") (pin "2") (pinfunction "2_2") (pintype "input"))
      (node (ref "SQW") (pin "1") (pinfunction "1_1") (pintype "unspecified"))
    )
    (net (code "107") (name "Net-(U1-VA1)") (class "Default")
      (node (ref "D7") (pin "1") (pinfunction "1_1") (pintype "unspecified"))
      (node (ref "RJ1") (pin "9") (pinfunction "9_9") (pintype "unspecified"))
      (node (ref "U1") (pin "1") (pinfunction "VA1_1") (pintype "unspecified"))
      (node (ref "U1") (pin "3") (pinfunction "VB1_3") (pintype "unspecified"))
    )
    (net (code "108") (name "Net-(U1-VA2)") (class "Default")
      (node (ref "D7") (pin "2") (pinfunction "2_2") (pintype "unspecified"))
      (node (ref "RJ1") (pin "10") (pinfunction "10_10") (pintype "unspecified"))
      (node (ref "U1") (pin "2") (pinfunction "VA2_2") (pintype "unspecified"))
      (node (ref "U1") (pin "4") (pinfunction "VB2_4") (pintype "unspecified"))
    )
    (net (code "109") (name "Net-(U2-CRS_DV{slash}MODE2)") (class "Default")
      (node (ref "R13") (pin "2") (pinfunction "2_2") (pintype "input"))
      (node (ref "U2") (pin "11") (pinfunction "CRS_DV/MODE2_11") (pintype "unspecified"))
    )
    (net (code "110") (name "Net-(U2-RBIAS)") (class "Default")
      (node (ref "R9") (pin "1") (pinfunction "1_1") (pintype "input"))
      (node (ref "U2") (pin "24") (pinfunction "RBIAS_24") (pintype "unspecified"))
    )
    (net (code "111") (name "Net-(U2-RXD0{slash}MODE0)") (class "Default")
      (node (ref "R12") (pin "2") (pinfunction "2_2") (pintype "input"))
      (node (ref "U2") (pin "8") (pinfunction "RXD0/MODE0_8") (pintype "unspecified"))
    )
    (net (code "112") (name "Net-(U2-RXD1{slash}MODE1)") (class "Default")
      (node (ref "R10") (pin "2") (pinfunction "2_2") (pintype "input"))
      (node (ref "U2") (pin "7") (pinfunction "RXD1/MODE1_7") (pintype "unspecified"))
    )
    (net (code "113") (name "Net-(U2-RXER{slash}PHYAD0)") (class "Default")
      (node (ref "R2") (pin "2") (pinfunction "2_2") (pintype "input"))
      (node (ref "U2") (pin "10") (pinfunction "RXER/PHYAD0_10") (pintype "unspecified"))
    )
    (net (code "114") (name "Net-(U2-VDDCR)") (class "Default")
      (node (ref "C8") (pin "1") (pinfunction "1_1") (pintype "input"))
      (node (ref "C9") (pin "1") (pinfunction "1_1") (pintype "unspecified"))
      (node (ref "U2") (pin "6") (pinfunction "VDDCR_6") (pintype "unspecified"))
    )
    (net (code "115") (name "Net-(U2-XTAL1{slash}CLKIN)") (class "Default")
      (node (ref "RN1") (pin "3") (pinfunction "3_3") (pintype "input"))
      (node (ref "U2") (pin "5") (pinfunction "XTAL1/CLKIN_5") (pintype "unspecified"))
    )
    (net (code "116") (name "Net-(U2-nINT{slash}REFCLKO)") (class "Default")
      (node (ref "RN1") (pin "8") (pinfunction "8_8") (pintype "input"))
      (node (ref "U2") (pin "14") (pinfunction "nINT/REFCLKO_14") (pintype "unspecified"))
    )
    (net (code "117") (name "Net-(U2-nRST)") (class "Default")
      (node (ref "C13") (pin "1") (pinfunction "1_1") (pintype "input"))
      (node (ref "R1") (pin "2") (pinfunction "2_2") (pintype "input"))
      (node (ref "U2") (pin "15") (pinfunction "nRST_15") (pintype "unspecified"))
    )
    (net (code "118") (name "Net-(U3-P0)") (class "Default")
      (node (ref "U3") (pin "4") (pinfunction "P0_4") (pintype "unspecified"))
      (node (ref "U4") (pin "1") (pinfunction "I1_1") (pintype "unspecified"))
    )
    (net (code "119") (name "Net-(U3-P1)") (class "Default")
      (node (ref "U3") (pin "5") (pinfunction "P1_5") (pintype "unspecified"))
      (node (ref "U4") (pin "2") (pinfunction "I2_2") (pintype "unspecified"))
    )
    (net (code "120") (name "Net-(U3-P2)") (class "Default")
      (node (ref "U3") (pin "6") (pinfunction "P2_6") (pintype "unspecified"))
      (node (ref "U4") (pin "3") (pinfunction "I3_3") (pintype "unspecified"))
    )
    (net (code "121") (name "Net-(U3-P3)") (class "Default")
      (node (ref "U3") (pin "7") (pinfunction "P3_7") (pintype "unspecified"))
      (node (ref "U4") (pin "4") (pinfunction "I4_4") (pintype "unspecified"))
    )
    (net (code "122") (name "Net-(U3-P4)") (class "Default")
      (node (ref "U3") (pin "9") (pinfunction "P4_9") (pintype "unspecified"))
      (node (ref "U4") (pin "5") (pinfunction "I5_5") (pintype "unspecified"))
    )
    (net (code "123") (name "Net-(U3-P5)") (class "Default")
      (node (ref "U3") (pin "10") (pinfunction "P5_10") (pintype "unspecified"))
      (node (ref "U4") (pin "6") (pinfunction "I6_6") (pintype "unspecified"))
    )
    (net (code "124") (name "Net-(U3-P6)") (class "Default")
      (node (ref "U3") (pin "11") (pinfunction "P6_11") (pintype "unspecified"))
      (node (ref "U4") (pin "7") (pinfunction "I7_7") (pintype "unspecified"))
    )
    (net (code "125") (name "Net-(U3-P7)") (class "Default")
      (node (ref "U3") (pin "12") (pinfunction "P7_12") (pintype "unspecified"))
      (node (ref "U4") (pin "8") (pinfunction "I8_8") (pintype "unspecified"))
    )
    (net (code "126") (name "Net-(U5-OUT)") (class "Default")
      (node (ref "C24") (pin "1") (pinfunction "1_1") (pintype "input"))
      (node (ref "R32") (pin "1") (pinfunction "1_1") (pintype "input"))
      (node (ref "U5") (pin "1") (pinfunction "OUT_1") (pintype "passive"))
      (node (ref "U6") (pin "2") (pinfunction "Input_2") (pintype "unspecified"))
    )
    (net (code "127") (name "Net-(U6-CD)") (class "Default")
      (node (ref "C26") (pin "2") (pinfunction "2_2") (pintype "input"))
      (node (ref "U6") (pin "5") (pinfunction "CD_5") (pintype "unspecified"))
    )
    (net (code "128") (name "Net-(U6-ResetOutput)") (class "Default")
      (node (ref "DRV") (pin "3") (pinfunction "3_3") (pintype "unspecified"))
      (node (ref "R32") (pin "2") (pinfunction "2_2") (pintype "input"))
      (node (ref "U6") (pin "1") (pinfunction "ResetOutput_1") (pintype "unspecified"))
    )
    (net (code "129") (name "Net-(U7-OUT)") (class "Default")
      (node (ref "C32") (pin "1") (pinfunction "1_1") (pintype "input"))
      (node (ref "U7") (pin "1") (pinfunction "OUT_1") (pintype "passive"))
      (node (ref "U9") (pin "8") (pinfunction "VCC_8") (pintype "unspecified"))
    )
    (net (code "130") (name "Net-(U8-INT#)") (class "Default")
      (node (ref "INT") (pin "3") (pinfunction "3_3") (pintype "unspecified"))
      (node (ref "R38") (pin "2") (pinfunction "2_2") (pintype "input"))
      (node (ref "U8") (pin "13") (pinfunction "INT#_13") (pintype "unspecified"))
    )
    (net (code "131") (name "Net-(U9-SQW{slash}OUT)") (class "Default")
      (node (ref "R40") (pin "2") (pinfunction "2_2") (pintype "input"))
      (node (ref "R42") (pin "1") (pinfunction "1_1") (pintype "input"))
      (node (ref "U9") (pin "7") (pinfunction "SQW/OUT_7") (pintype "unspecified"))
    )
    (net (code "132") (name "Net-(U9-VBAT)") (class "Default")
      (node (ref "BT1") (pin "1") (pinfunction "1_1") (pintype "input"))
      (node (ref "U9") (pin "3") (pinfunction "VBAT_3") (pintype "unspecified"))
    )
    (net (code "133") (name "Net-(U9-X1)") (class "Default")
      (node (ref "U9") (pin "1") (pinfunction "X1_1") (pintype "unspecified"))
      (node (ref "X2") (pin "1") (pinfunction "OSC1_1") (pintype "input"))
    )
    (net (code "134") (name "Net-(U9-X2)") (class "Default")
      (node (ref "U9") (pin "2") (pinfunction "X2_2") (pintype "unspecified"))
      (node (ref "X2") (pin "2") (pinfunction "OSC2_2") (pintype "input"))
    )
    (net (code "135") (name "Net-(U10-IO14)") (class "Default")
      (node (ref "R49") (pin "1") (pinfunction "1_1") (pintype "input"))
      (node (ref "R50") (pin "1") (pinfunction "1_1") (pintype "input"))
      (node (ref "U10") (pin "13") (pinfunction "IO14_13") (pintype "unspecified"))
    )
    (net (code "136") (name "Net-(U10-RXD0)") (class "Default")
      (node (ref "PGM") (pin "3") (pinfunction "3_3") (pintype "unspecified"))
      (node (ref "U10") (pin "34") (pinfunction "RXD0_34") (pintype "unspecified"))
    )
    (net (code "137") (name "Net-(U10-TXD0)") (class "Default")
      (node (ref "PGM") (pin "2") (pinfunction "2_2") (pintype "unspecified"))
      (node (ref "U10") (pin "35") (pinfunction "TXD0_35") (pintype "unspecified"))
    )
    (net (code "138") (name "Net-(X1-Enable{slash}Disable)") (class "Default")
      (node (ref "R16") (pin "2") (pinfunction "2_2") (pintype "input"))
      (node (ref "R17") (pin "1") (pinfunction "1_1") (pintype "input"))
      (node (ref "X1") (pin "1") (pinfunction "Enable/Disable_1") (pintype "unspecified"))
    )
    (net (code "139") (name "Net-(X1-OUT)") (class "Default")
      (node (ref "RN1") (pin "6") (pinfunction "6_6") (pintype "input"))
      (node (ref "RN1") (pin "7") (pinfunction "7_7") (pintype "input"))
      (node (ref "X1") (pin "3") (pinfunction "OUT_3") (pintype "unspecified"))
    )
    (net (code "140") (name "PHY_PWR") (class "Default")
      (node (ref "P14") (pin "11") (pinfunction "11_11") (pintype "input"))
      (node (ref "PHY") (pin "2") (pinfunction "2_2") (pintype "unspecified"))
      (node (ref "U10") (pin "28") (pinfunction "IO17_28") (pintype "unspecified"))
    )
    (net (code "141") (name "RD+") (class "Default")
      (node (ref "D2") (pin "2") (pinfunction "2_2") (pintype "unspecified"))
      (node (ref "R4") (pin "2") (pinfunction "2_2") (pintype "input"))
      (node (ref "RJ1") (pin "1") (pinfunction "1_1") (pintype "unspecified"))
      (node (ref "U2") (pin "23") (pinfunction "RXP_23") (pintype "unspecified"))
    )
    (net (code "142") (name "RD-") (class "Default")
      (node (ref "D1") (pin "1") (pinfunction "1_1") (pintype "unspecified"))
      (node (ref "R5") (pin "2") (pinfunction "2_2") (pintype "input"))
      (node (ref "RJ1") (pin "2") (pinfunction "2_2") (pintype "unspecified"))
      (node (ref "U2") (pin "22") (pinfunction "RXN_22") (pintype "unspecified"))
    )
    (net (code "143") (name "RELAY_0") (class "Default")
      (node (ref "D14") (pin "1") (pinfunction "-_1") (pintype "unspecified"))
      (node (ref "LED8") (pin "1") (pinfunction "A_1") (pintype "input"))
      (node (ref "RELAY1") (pin "1") (pinfunction "1_1") (pintype "input"))
      (node (ref "U4") (pin "18") (pinfunction "O1_18") (pintype "unspecified"))
    )
    (net (code "144") (name "RELAY_1") (class "Default")
      (node (ref "D15") (pin "1") (pinfunction "-_1") (pintype "unspecified"))
      (node (ref "LED6") (pin "1") (pinfunction "A_1") (pintype "input"))
      (node (ref "RELAY2") (pin "1") (pinfunction "1_1") (pintype "input"))
      (node (ref "U4") (pin "17") (pinfunction "O2_17") (pintype "unspecified"))
    )
    (net (code "145") (name "RELAY_2") (class "Default")
      (node (ref "D16") (pin "1") (pinfunction "-_1") (pintype "unspecified"))
      (node (ref "LED4") (pin "1") (pinfunction "A_1") (pintype "input"))
      (node (ref "RELAY3") (pin "1") (pinfunction "1_1") (pintype "input"))
      (node (ref "U4") (pin "16") (pinfunction "O3_16") (pintype "unspecified"))
    )
    (net (code "146") (name "RELAY_3") (class "Default")
      (node (ref "D17") (pin "1") (pinfunction "-_1") (pintype "unspecified"))
      (node (ref "LED2") (pin "1") (pinfunction "A_1") (pintype "input"))
      (node (ref "RELAY4") (pin "1") (pinfunction "1_1") (pintype "input"))
      (node (ref "U4") (pin "15") (pinfunction "O4_15") (pintype "unspecified"))
    )
    (net (code "147") (name "RELAY_4") (class "Default")
      (node (ref "D22") (pin "1") (pinfunction "-_1") (pintype "unspecified"))
      (node (ref "LED9") (pin "1") (pinfunction "A_1") (pintype "input"))
      (node (ref "RELAY5") (pin "1") (pinfunction "1_1") (pintype "input"))
      (node (ref "U4") (pin "14") (pinfunction "O5_14") (pintype "unspecified"))
    )
    (net (code "148") (name "RELAY_5") (class "Default")
      (node (ref "D23") (pin "1") (pinfunction "-_1") (pintype "unspecified"))
      (node (ref "LED7") (pin "1") (pinfunction "A_1") (pintype "input"))
      (node (ref "RELAY6") (pin "1") (pinfunction "1_1") (pintype "input"))
      (node (ref "U4") (pin "13") (pinfunction "O6_13") (pintype "unspecified"))
    )
    (net (code "149") (name "RELAY_6") (class "Default")
      (node (ref "D24") (pin "1") (pinfunction "-_1") (pintype "unspecified"))
      (node (ref "LED5") (pin "1") (pinfunction "A_1") (pintype "input"))
      (node (ref "RELAY7") (pin "1") (pinfunction "1_1") (pintype "input"))
      (node (ref "U4") (pin "12") (pinfunction "O7_12") (pintype "unspecified"))
    )
    (net (code "150") (name "RELAY_7") (class "Default")
      (node (ref "D25") (pin "1") (pinfunction "-_1") (pintype "unspecified"))
      (node (ref "LED3") (pin "1") (pinfunction "A_1") (pintype "input"))
      (node (ref "RELAY8") (pin "1") (pinfunction "1_1") (pintype "input"))
      (node (ref "U4") (pin "11") (pinfunction "O8_11") (pintype "unspecified"))
    )
    (net (code "151") (name "RLY_CTRL") (class "Default")
      (node (ref "DRV") (pin "1") (pinfunction "1_1") (pintype "unspecified"))
      (node (ref "P14") (pin "7") (pinfunction "7_7") (pintype "input"))
      (node (ref "U10") (pin "27") (pinfunction "IO16_27") (pintype "unspecified"))
    )
    (net (code "152") (name "RTS") (class "Default")
      (node (ref "PGM") (pin "5") (pinfunction "5_5") (pintype "unspecified"))
      (node (ref "Q4") (pin "2") (pinfunction "E_2") (pintype "unspecified"))
      (node (ref "R39") (pin "2") (pinfunction "2_2") (pintype "input"))
    )
    (net (code "153") (name "SQW") (class "Default")
      (node (ref "P14") (pin "5") (pinfunction "5_5") (pintype "input"))
      (node (ref "SQW") (pin "2") (pinfunction "2_2") (pintype "unspecified"))
      (node (ref "U10") (pin "14") (pinfunction "IO12_14") (pintype "unspecified"))
    )
    (net (code "154") (name "TD+") (class "Default")
      (node (ref "D4") (pin "2") (pinfunction "2_2") (pintype "unspecified"))
      (node (ref "R6") (pin "2") (pinfunction "2_2") (pintype "input"))
      (node (ref "RJ1") (pin "5") (pinfunction "5_5") (pintype "unspecified"))
      (node (ref "U2") (pin "21") (pinfunction "TXP_21") (pintype "unspecified"))
    )
    (net (code "155") (name "TD-") (class "Default")
      (node (ref "D3") (pin "1") (pinfunction "1_1") (pintype "unspecified"))
      (node (ref "R7") (pin "2") (pinfunction "2_2") (pintype "input"))
      (node (ref "RJ1") (pin "6") (pinfunction "6_6") (pintype "unspecified"))
      (node (ref "U2") (pin "20") (pinfunction "TXN_20") (pintype "unspecified"))
    )
    (net (code "156") (name "unconnected-(BOOT-A-Pad1)") (class "Default")
      (node (ref "BOOT") (pin "1") (pinfunction "A_1") (pintype "unspecified+no_connect"))
    )
    (net (code "157") (name "unconnected-(BOOT-D-Pad4)") (class "Default")
      (node (ref "BOOT") (pin "4") (pinfunction "D_4") (pintype "unspecified+no_connect"))
    )
    (net (code "158") (name "unconnected-(EN-A-Pad1)") (class "Default")
      (node (ref "EN") (pin "1") (pinfunction "A_1") (pintype "unspecified+no_connect"))
    )
    (net (code "159") (name "unconnected-(EN-D-Pad4)") (class "Default")
      (node (ref "EN") (pin "4") (pinfunction "D_4") (pintype "unspecified+no_connect"))
    )
    (net (code "160") (name "unconnected-(INT-Pad1)") (class "Default")
      (node (ref "INT") (pin "1") (pinfunction "1_1") (pintype "unspecified+no_connect"))
    )
    (net (code "161") (name "unconnected-(IO1-Pad3)") (class "Default")
      (node (ref "IO1") (pin "3") (pinfunction "3_3") (pintype "unspecified+no_connect"))
    )
    (net (code "162") (name "unconnected-(IO2-Pad3)") (class "Default")
      (node (ref "IO2") (pin "3") (pinfunction "3_3") (pintype "unspecified+no_connect"))
    )
    (net (code "163") (name "unconnected-(PGM-Pad4)") (class "Default")
      (node (ref "PGM") (pin "4") (pinfunction "4_4") (pintype "unspecified+no_connect"))
    )
    (net (code "164") (name "unconnected-(PHY-Pad3)") (class "Default")
      (node (ref "PHY") (pin "3") (pinfunction "3_3") (pintype "unspecified+no_connect"))
    )
    (net (code "165") (name "unconnected-(RF1-SIG-Pad1)") (class "Default")
      (node (ref "RF1") (pin "1") (pinfunction "SIG_1") (pintype "unspecified"))
    )
    (net (code "166") (name "unconnected-(RJ1-Pad7)") (class "Default")
      (node (ref "RJ1") (pin "7") (pinfunction "7_7") (pintype "unspecified+no_connect"))
    )
    (net (code "167") (name "unconnected-(RJ1-Pad8)") (class "Default")
      (node (ref "RJ1") (pin "8") (pinfunction "8_8") (pintype "unspecified+no_connect"))
    )
    (net (code "168") (name "unconnected-(RN1-Pad4)") (class "Default")
      (node (ref "RN1") (pin "4") (pinfunction "4_4") (pintype "input+no_connect"))
    )
    (net (code "169") (name "unconnected-(RN1-Pad5)") (class "Default")
      (node (ref "RN1") (pin "5") (pinfunction "5_5") (pintype "input+no_connect"))
    )
    (net (code "170") (name "unconnected-(SQW-Pad3)") (class "Default")
      (node (ref "SQW") (pin "3") (pinfunction "3_3") (pintype "unspecified+no_connect"))
    )
    (net (code "171") (name "unconnected-(U1-AT{slash}DET+-Pad5)") (class "Default")
      (node (ref "U1") (pin "5") (pinfunction "AT/DET+_5") (pintype "unspecified+no_connect"))
    )
    (net (code "172") (name "unconnected-(U1-GND-Pad6)") (class "Default")
      (node (ref "U1") (pin "6") (pinfunction "GND_6") (pintype "unspecified+no_connect"))
    )
    (net (code "173") (name "unconnected-(U2-XTAL2-Pad4)") (class "Default")
      (node (ref "U2") (pin "4") (pinfunction "XTAL2_4") (pintype "unspecified+no_connect"))
    )
    (net (code "174") (name "unconnected-(U3-INT#-Pad13)") (class "Default")
      (node (ref "U3") (pin "13") (pinfunction "INT#_13") (pintype "unspecified+no_connect"))
    )
    (net (code "175") (name "unconnected-(U6-N.C.-Pad4)") (class "Default")
      (node (ref "U6") (pin "4") (pinfunction "N.C._4") (pintype "unspecified+no_connect"))
    )
    (net (code "176") (name "unconnected-(U10-CLK-Pad20)") (class "Default")
      (node (ref "U10") (pin "20") (pinfunction "CLK_20") (pintype "unspecified+no_connect"))
    )
    (net (code "177") (name "unconnected-(U10-CMD-Pad19)") (class "Default")
      (node (ref "U10") (pin "19") (pinfunction "CMD_19") (pintype "unspecified+no_connect"))
    )
    (net (code "178") (name "unconnected-(U10-IO2-Pad24)") (class "Default")
      (node (ref "U10") (pin "24") (pinfunction "IO2_24") (pintype "unspecified+no_connect"))
    )
    (net (code "179") (name "unconnected-(U10-IO15-Pad23)") (class "Default")
      (node (ref "U10") (pin "23") (pinfunction "IO15_23") (pintype "unspecified+no_connect"))
    )
    (net (code "180") (name "unconnected-(U10-IO34-Pad6)") (class "Default")
      (node (ref "U10") (pin "6") (pinfunction "IO34_6") (pintype "unspecified+no_connect"))
    )
    (net (code "181") (name "unconnected-(U10-IO35-Pad7)") (class "Default")
      (node (ref "U10") (pin "7") (pinfunction "IO35_7") (pintype "unspecified+no_connect"))
    )
    (net (code "182") (name "unconnected-(U10-NC-Pad32)") (class "Default")
      (node (ref "U10") (pin "32") (pinfunction "NC_32") (pintype "unspecified+no_connect"))
    )
    (net (code "183") (name "unconnected-(U10-SD0-Pad21)") (class "Default")
      (node (ref "U10") (pin "21") (pinfunction "SD0_21") (pintype "unspecified+no_connect"))
    )
    (net (code "184") (name "unconnected-(U10-SD1-Pad22)") (class "Default")
      (node (ref "U10") (pin "22") (pinfunction "SD1_22") (pintype "unspecified+no_connect"))
    )
    (net (code "185") (name "unconnected-(U10-SD2-Pad17)") (class "Default")
      (node (ref "U10") (pin "17") (pinfunction "SD2_17") (pintype "unspecified+no_connect"))
    )
    (net (code "186") (name "unconnected-(U10-SD3-Pad18)") (class "Default")
      (node (ref "U10") (pin "18") (pinfunction "SD3_18") (pintype "unspecified+no_connect"))
    )
    (net (code "187") (name "unconnected-(U10-SENSOR_VN-Pad5)") (class "Default")
      (node (ref "U10") (pin "5") (pinfunction "SENSOR_VN_5") (pintype "unspecified+no_connect"))
    )
    (net (code "188") (name "unconnected-(U10-SENSOR_VP-Pad4)") (class "Default")
      (node (ref "U10") (pin "4") (pinfunction "SENSOR_VP_4") (pintype "unspecified+no_connect"))
    )
  )
)
